# DC_AC_Inverter.net
KiCad netlist of a schematic drawn in Altium Designer
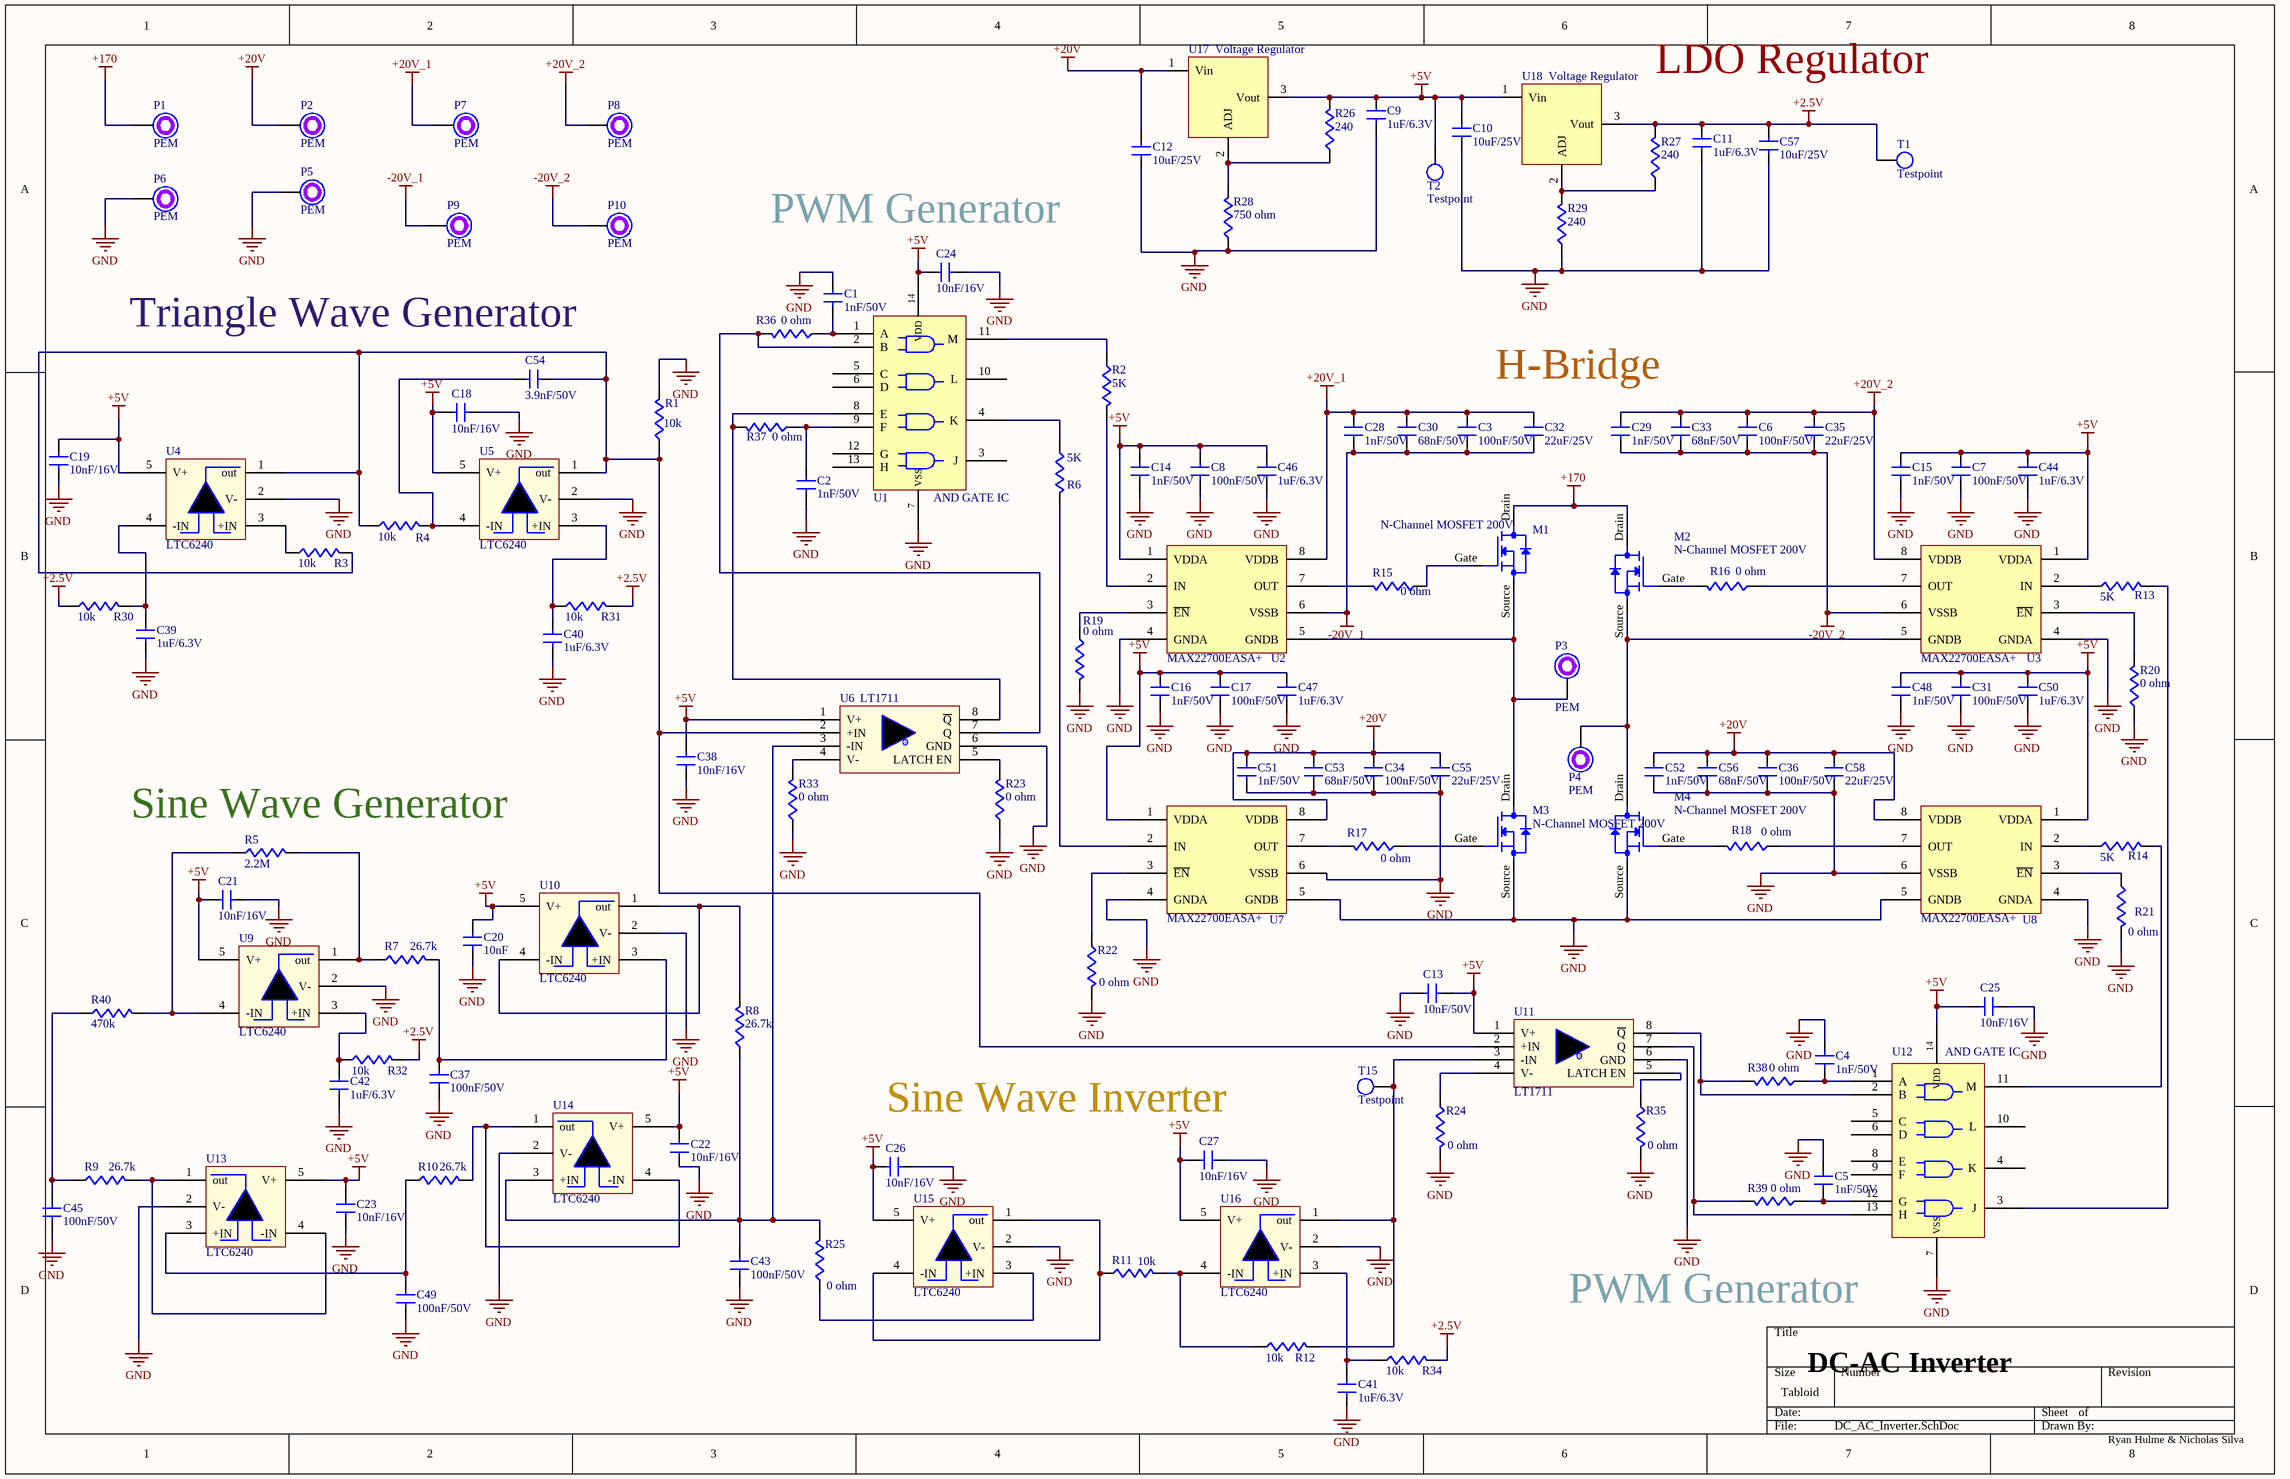
[diagram p0: DC_AC_Inverter.SchDoc]

(export (version "E")
  (design (tool "Eeschema 10.0.6"))
  (components
    (comp (ref "C1")
      (value "1nF/50V")
      (footprint "Capacitor")
      (description "Multilayer Ceramic Capacitors Mlcc - Smd/Smt 50V 1000Pf X7R 0603 10%")
      (fields
        (field (name "MANUFACTURER") "KEMET")
        (field (name "MANUFACTURER PART NUMBER") "C0603C102K5RACTU")
      )
      (libsource (lib "MAX227") (part "C0603C102K5RACTU"))
    )
    (comp (ref "C2")
      (value "1nF/50V")
      (footprint "Capacitor")
      (description "Multilayer Ceramic Capacitors Mlcc - Smd/Smt 50V 1000Pf X7R 0603 10%")
      (fields
        (field (name "MANUFACTURER") "KEMET")
        (field (name "MANUFACTURER PART NUMBER") "C0603C102K5RACTU")
      )
      (libsource (lib "MAX227") (part "C0603C102K5RACTU"))
    )
    (comp (ref "C3")
      (value "100nF/50V")
      (footprint "Capacitor")
      (description "50V 100nF X7R ±10% 0603 Multilayer Ceramic Capacitors MLCC - SMD/SMT ROHS")
      (fields
        (field (name "MANUFACTURER") "KEMET")
        (field (name "MANUFACTURER PART NUMBER") "C0603C104K5RACTU")
      )
      (libsource (lib "MAX227") (part "C0603C104K5RACTU"))
    )
    (comp (ref "C4")
      (value "1nF/50V")
      (footprint "Capacitor")
      (description "Multilayer Ceramic Capacitors Mlcc - Smd/Smt 50V 1000Pf X7R 0603 10%")
      (fields
        (field (name "MANUFACTURER") "KEMET")
        (field (name "MANUFACTURER PART NUMBER") "C0603C102K5RACTU")
      )
      (libsource (lib "MAX227") (part "C0603C102K5RACTU"))
    )
    (comp (ref "C5")
      (value "1nF/50V")
      (footprint "Capacitor")
      (description "Multilayer Ceramic Capacitors Mlcc - Smd/Smt 50V 1000Pf X7R 0603 10%")
      (fields
        (field (name "MANUFACTURER") "KEMET")
        (field (name "MANUFACTURER PART NUMBER") "C0603C102K5RACTU")
      )
      (libsource (lib "MAX227") (part "C0603C102K5RACTU"))
    )
    (comp (ref "C6")
      (value "100nF/50V")
      (footprint "Capacitor")
      (description "50V 100nF X7R ±10% 0603 Multilayer Ceramic Capacitors MLCC - SMD/SMT ROHS")
      (fields
        (field (name "MANUFACTURER") "KEMET")
        (field (name "MANUFACTURER PART NUMBER") "C0603C104K5RACTU")
      )
      (libsource (lib "MAX227") (part "C0603C104K5RACTU"))
    )
    (comp (ref "C7")
      (value "100nF/50V")
      (footprint "Capacitor")
      (description "50V 100nF X7R ±10% 0603 Multilayer Ceramic Capacitors MLCC - SMD/SMT ROHS")
      (fields
        (field (name "MANUFACTURER") "KEMET")
        (field (name "MANUFACTURER PART NUMBER") "C0603C104K5RACTU")
      )
      (libsource (lib "MAX227") (part "C0603C104K5RACTU"))
    )
    (comp (ref "C8")
      (value "100nF/50V")
      (footprint "Capacitor")
      (description "50V 100nF X7R ±10% 0603 Multilayer Ceramic Capacitors MLCC - SMD/SMT ROHS")
      (fields
        (field (name "MANUFACTURER") "KEMET")
        (field (name "MANUFACTURER PART NUMBER") "C0603C104K5RACTU")
      )
      (libsource (lib "MAX227") (part "C0603C104K5RACTU"))
    )
    (comp (ref "C9")
      (value "1uF/6.3V")
      (footprint "Capacitor")
      (description "High Value Multilayer Ceramic Capacitors (High dielectric type) ¦ CAP CER 1UF 6.3V X5R 0402")
      (fields
        (field (name "MANUFACTURER") "Taiyo Yuden")
        (field (name "MANUFACTURER PART NUMBER") "JMK105BJ105KV-F")
      )
      (libsource (lib "MAX227") (part "JMK105BJ105KV-F"))
    )
    (comp (ref "C10")
      (value "10uF/25V")
      (footprint "Capacitor")
      (description "25V 10uF X5R ±20% 0603 Multilayer Ceramic Capacitors MLCC - SMD/SMT ROHS")
      (fields
        (field (name "MANUFACTURER") "Samsung Electro-Mechanics")
        (field (name "MANUFACTURER PART NUMBER") "CL10A106MA8NRNC")
      )
      (libsource (lib "MAX227") (part "CL10A106MA8NRNC"))
    )
    (comp (ref "C11")
      (value "1uF/6.3V")
      (footprint "Capacitor")
      (description "High Value Multilayer Ceramic Capacitors (High dielectric type) ¦ CAP CER 1UF 6.3V X5R 0402")
      (fields
        (field (name "MANUFACTURER") "Taiyo Yuden")
        (field (name "MANUFACTURER PART NUMBER") "JMK105BJ105KV-F")
      )
      (libsource (lib "MAX227") (part "JMK105BJ105KV-F"))
    )
    (comp (ref "C12")
      (value "10uF/25V")
      (footprint "Capacitor")
      (description "25V 10uF X5R ±20% 0603 Multilayer Ceramic Capacitors MLCC - SMD/SMT ROHS")
      (fields
        (field (name "MANUFACTURER") "Samsung Electro-Mechanics")
        (field (name "MANUFACTURER PART NUMBER") "CL10A106MA8NRNC")
      )
      (libsource (lib "MAX227") (part "CL10A106MA8NRNC"))
    )
    (comp (ref "C13")
      (value "10nF/50V")
      (footprint "Capacitor")
      (description "16V 10nF X7R ±10% 0402 Multilayer Ceramic Capacitors MLCC - SMD/SMT ROHS")
      (fields
        (field (name "MANUFACTURER") "Murata")
        (field (name "MANUFACTURER PART NUMBER") "GRM155R71C103KA01D")
      )
      (libsource (lib "MAX227") (part "GRM155R71C103KA01D"))
    )
    (comp (ref "C14")
      (value "1nF/50V")
      (footprint "Capacitor")
      (description "Multilayer Ceramic Capacitors Mlcc - Smd/Smt 50V 1000Pf X7R 0603 10%")
      (fields
        (field (name "MANUFACTURER") "KEMET")
        (field (name "MANUFACTURER PART NUMBER") "C0603C102K5RACTU")
      )
      (libsource (lib "MAX227") (part "C0603C102K5RACTU"))
    )
    (comp (ref "C15")
      (value "1nF/50V")
      (footprint "Capacitor")
      (description "Multilayer Ceramic Capacitors Mlcc - Smd/Smt 50V 1000Pf X7R 0603 10%")
      (fields
        (field (name "MANUFACTURER") "KEMET")
        (field (name "MANUFACTURER PART NUMBER") "C0603C102K5RACTU")
      )
      (libsource (lib "MAX227") (part "C0603C102K5RACTU"))
    )
    (comp (ref "C16")
      (value "1nF/50V")
      (footprint "Capacitor")
      (description "Multilayer Ceramic Capacitors Mlcc - Smd/Smt 50V 1000Pf X7R 0603 10%")
      (fields
        (field (name "MANUFACTURER") "KEMET")
        (field (name "MANUFACTURER PART NUMBER") "C0603C102K5RACTU")
      )
      (libsource (lib "MAX227") (part "C0603C102K5RACTU"))
    )
    (comp (ref "C17")
      (value "100nF/50V")
      (footprint "Capacitor")
      (description "50V 100nF X7R ±10% 0603 Multilayer Ceramic Capacitors MLCC - SMD/SMT ROHS")
      (fields
        (field (name "MANUFACTURER") "KEMET")
        (field (name "MANUFACTURER PART NUMBER") "C0603C104K5RACTU")
      )
      (libsource (lib "MAX227") (part "C0603C104K5RACTU"))
    )
    (comp (ref "C18")
      (value "10nF/16V")
      (footprint "Capacitor")
      (description "16V 10nF X7R ±10% 0402 Multilayer Ceramic Capacitors MLCC - SMD/SMT ROHS")
      (fields
        (field (name "MANUFACTURER") "Murata")
        (field (name "MANUFACTURER PART NUMBER") "GRM155R71C103KA01D")
      )
      (libsource (lib "MAX227") (part "GRM155R71C103KA01D"))
    )
    (comp (ref "C19")
      (value "10nF/16V")
      (footprint "Capacitor")
      (description "16V 10nF X7R ±10% 0402 Multilayer Ceramic Capacitors MLCC - SMD/SMT ROHS")
      (fields
        (field (name "MANUFACTURER") "Murata")
        (field (name "MANUFACTURER PART NUMBER") "GRM155R71C103KA01D")
      )
      (libsource (lib "MAX227") (part "GRM155R71C103KA01D"))
    )
    (comp (ref "C20")
      (value "10nF")
      (footprint "Capacitor")
      (description "16V 10nF X7R ±10% 0402 Multilayer Ceramic Capacitors MLCC - SMD/SMT ROHS")
      (fields
        (field (name "MANUFACTURER") "Murata")
        (field (name "MANUFACTURER PART NUMBER") "GRM155R71C103KA01D")
      )
      (libsource (lib "MAX227") (part "GRM155R71C103KA01D"))
    )
    (comp (ref "C21")
      (value "10nF/16V")
      (footprint "Capacitor")
      (description "16V 10nF X7R ±10% 0402 Multilayer Ceramic Capacitors MLCC - SMD/SMT ROHS")
      (fields
        (field (name "MANUFACTURER") "Murata")
        (field (name "MANUFACTURER PART NUMBER") "GRM155R71C103KA01D")
      )
      (libsource (lib "MAX227") (part "GRM155R71C103KA01D"))
    )
    (comp (ref "C22")
      (value "10nF/16V")
      (footprint "Capacitor")
      (description "16V 10nF X7R ±10% 0402 Multilayer Ceramic Capacitors MLCC - SMD/SMT ROHS")
      (fields
        (field (name "MANUFACTURER") "Murata")
        (field (name "MANUFACTURER PART NUMBER") "GRM155R71C103KA01D")
      )
      (libsource (lib "MAX227") (part "GRM155R71C103KA01D"))
    )
    (comp (ref "C23")
      (value "10nF/16V")
      (footprint "Capacitor")
      (description "16V 10nF X7R ±10% 0402 Multilayer Ceramic Capacitors MLCC - SMD/SMT ROHS")
      (fields
        (field (name "MANUFACTURER") "Murata")
        (field (name "MANUFACTURER PART NUMBER") "GRM155R71C103KA01D")
      )
      (libsource (lib "MAX227") (part "GRM155R71C103KA01D"))
    )
    (comp (ref "C24")
      (value "10nF/16V")
      (footprint "Capacitor")
      (description "16V 10nF X7R ±10% 0402 Multilayer Ceramic Capacitors MLCC - SMD/SMT ROHS")
      (fields
        (field (name "MANUFACTURER") "Murata")
        (field (name "MANUFACTURER PART NUMBER") "GRM155R71C103KA01D")
      )
      (libsource (lib "MAX227") (part "GRM155R71C103KA01D"))
    )
    (comp (ref "C25")
      (value "10nF/16V")
      (footprint "Capacitor")
      (description "16V 10nF X7R ±10% 0402 Multilayer Ceramic Capacitors MLCC - SMD/SMT ROHS")
      (fields
        (field (name "MANUFACTURER") "Murata")
        (field (name "MANUFACTURER PART NUMBER") "GRM155R71C103KA01D")
      )
      (libsource (lib "MAX227") (part "GRM155R71C103KA01D"))
    )
    (comp (ref "C26")
      (value "10nF/16V")
      (footprint "Capacitor")
      (description "16V 10nF X7R ±10% 0402 Multilayer Ceramic Capacitors MLCC - SMD/SMT ROHS")
      (fields
        (field (name "MANUFACTURER") "Murata")
        (field (name "MANUFACTURER PART NUMBER") "GRM155R71C103KA01D")
      )
      (libsource (lib "MAX227") (part "GRM155R71C103KA01D"))
    )
    (comp (ref "C27")
      (value "10nF/16V")
      (footprint "Capacitor")
      (description "16V 10nF X7R ±10% 0402 Multilayer Ceramic Capacitors MLCC - SMD/SMT ROHS")
      (fields
        (field (name "MANUFACTURER") "Murata")
        (field (name "MANUFACTURER PART NUMBER") "GRM155R71C103KA01D")
      )
      (libsource (lib "MAX227") (part "GRM155R71C103KA01D"))
    )
    (comp (ref "C28")
      (value "1nF/50V")
      (footprint "Capacitor")
      (description "Multilayer Ceramic Capacitors Mlcc - Smd/Smt 50V 1000Pf X7R 0603 10%")
      (fields
        (field (name "MANUFACTURER") "KEMET")
        (field (name "MANUFACTURER PART NUMBER") "C0603C102K5RACTU")
      )
      (libsource (lib "MAX227") (part "C0603C102K5RACTU"))
    )
    (comp (ref "C29")
      (value "1nF/50V")
      (footprint "Capacitor")
      (description "Multilayer Ceramic Capacitors Mlcc - Smd/Smt 50V 1000Pf X7R 0603 10%")
      (fields
        (field (name "MANUFACTURER") "KEMET")
        (field (name "MANUFACTURER PART NUMBER") "C0603C102K5RACTU")
      )
      (libsource (lib "MAX227") (part "C0603C102K5RACTU"))
    )
    (comp (ref "C30")
      (value "68nF/50V")
      (footprint "Capacitor")
      (fields
        (field (name "MANUFACTURER") "KEMET")
        (field (name "MANUFACTURER PART NUMBER") "C0603C683K5RACTU")
        (field (name "TOLERANCE") "10%")
      )
      (libsource (lib "MAX227") (part "C0603C683K5RACTU"))
    )
    (comp (ref "C31")
      (value "100nF/50V")
      (footprint "Capacitor")
      (description "50V 100nF X7R ±10% 0603 Multilayer Ceramic Capacitors MLCC - SMD/SMT ROHS")
      (fields
        (field (name "MANUFACTURER") "KEMET")
        (field (name "MANUFACTURER PART NUMBER") "C0603C104K5RACTU")
      )
      (libsource (lib "MAX227") (part "C0603C104K5RACTU"))
    )
    (comp (ref "C32")
      (value "22uF/25V")
      (footprint "Capacitor")
      (fields
        (field (name "MANUFACTURER") "Murata")
        (field (name "MANUFACTURER PART NUMBER") "GRM188C61E226ME01J")
        (field (name "TOLERANCE") "20%")
      )
      (libsource (lib "MAX227") (part "GRM188C61E226ME01J"))
    )
    (comp (ref "C33")
      (value "68nF/50V")
      (footprint "Capacitor")
      (fields
        (field (name "MANUFACTURER") "KEMET")
        (field (name "MANUFACTURER PART NUMBER") "C0603C683K5RACTU")
        (field (name "TOLERANCE") "10%")
      )
      (libsource (lib "MAX227") (part "C0603C683K5RACTU"))
    )
    (comp (ref "C34")
      (value "100nF/50V")
      (footprint "Capacitor")
      (description "50V 100nF X7R ±10% 0603 Multilayer Ceramic Capacitors MLCC - SMD/SMT ROHS")
      (fields
        (field (name "MANUFACTURER") "KEMET")
        (field (name "MANUFACTURER PART NUMBER") "C0603C104K5RACTU")
      )
      (libsource (lib "MAX227") (part "C0603C104K5RACTU"))
    )
    (comp (ref "C35")
      (value "22uF/25V")
      (footprint "Capacitor")
      (fields
        (field (name "MANUFACTURER") "Murata")
        (field (name "MANUFACTURER PART NUMBER") "GRM188C61E226ME01J")
        (field (name "TOLERANCE") "20%")
      )
      (libsource (lib "MAX227") (part "GRM188C61E226ME01J"))
    )
    (comp (ref "C36")
      (value "100nF/50V")
      (footprint "Capacitor")
      (description "50V 100nF X7R ±10% 0603 Multilayer Ceramic Capacitors MLCC - SMD/SMT ROHS")
      (fields
        (field (name "MANUFACTURER") "KEMET")
        (field (name "MANUFACTURER PART NUMBER") "C0603C104K5RACTU")
      )
      (libsource (lib "MAX227") (part "C0603C104K5RACTU"))
    )
    (comp (ref "C37")
      (value "100nF/50V")
      (footprint "Capacitor")
      (description "50V 100nF X7R ±10% 0603 Multilayer Ceramic Capacitors MLCC - SMD/SMT ROHS")
      (fields
        (field (name "MANUFACTURER") "KEMET")
        (field (name "MANUFACTURER PART NUMBER") "C0603C104K5RACTU")
      )
      (libsource (lib "MAX227") (part "C0603C104K5RACTU"))
    )
    (comp (ref "C38")
      (value "10nF/16V")
      (footprint "Capacitor")
      (description "16V 10nF X7R ±10% 0402 Multilayer Ceramic Capacitors MLCC - SMD/SMT ROHS")
      (fields
        (field (name "MANUFACTURER") "Murata")
        (field (name "MANUFACTURER PART NUMBER") "GRM155R71C103KA01D")
      )
      (libsource (lib "MAX227") (part "GRM155R71C103KA01D"))
    )
    (comp (ref "C39")
      (value "1uF/6.3V")
      (footprint "Capacitor")
      (description "High Value Multilayer Ceramic Capacitors (High dielectric type) ¦ CAP CER 1UF 6.3V X5R 0402")
      (fields
        (field (name "MANUFACTURER") "Taiyo Yuden")
        (field (name "MANUFACTURER PART NUMBER") "JMK105BJ105KV-F")
      )
      (libsource (lib "MAX227") (part "JMK105BJ105KV-F"))
    )
    (comp (ref "C40")
      (value "1uF/6.3V")
      (footprint "Capacitor")
      (description "High Value Multilayer Ceramic Capacitors (High dielectric type) ¦ CAP CER 1UF 6.3V X5R 0402")
      (fields
        (field (name "MANUFACTURER") "Taiyo Yuden")
        (field (name "MANUFACTURER PART NUMBER") "JMK105BJ105KV-F")
      )
      (libsource (lib "MAX227") (part "JMK105BJ105KV-F"))
    )
    (comp (ref "C41")
      (value "1uF/6.3V")
      (footprint "Capacitor")
      (description "High Value Multilayer Ceramic Capacitors (High dielectric type) ¦ CAP CER 1UF 6.3V X5R 0402")
      (fields
        (field (name "MANUFACTURER") "Taiyo Yuden")
        (field (name "MANUFACTURER PART NUMBER") "JMK105BJ105KV-F")
      )
      (libsource (lib "MAX227") (part "JMK105BJ105KV-F"))
    )
    (comp (ref "C42")
      (value "1uF/6.3V")
      (footprint "Capacitor")
      (description "High Value Multilayer Ceramic Capacitors (High dielectric type) ¦ CAP CER 1UF 6.3V X5R 0402")
      (fields
        (field (name "MANUFACTURER") "Taiyo Yuden")
        (field (name "MANUFACTURER PART NUMBER") "JMK105BJ105KV-F")
      )
      (libsource (lib "MAX227") (part "JMK105BJ105KV-F"))
    )
    (comp (ref "C43")
      (value "100nF/50V")
      (footprint "Capacitor")
      (description "50V 100nF X7R ±10% 0603 Multilayer Ceramic Capacitors MLCC - SMD/SMT ROHS")
      (fields
        (field (name "MANUFACTURER") "KEMET")
        (field (name "MANUFACTURER PART NUMBER") "C0603C104K5RACTU")
      )
      (libsource (lib "MAX227") (part "C0603C104K5RACTU"))
    )
    (comp (ref "C44")
      (value "1uF/6.3V")
      (footprint "Capacitor")
      (description "High Value Multilayer Ceramic Capacitors (High dielectric type) ¦ CAP CER 1UF 6.3V X5R 0402")
      (fields
        (field (name "MANUFACTURER") "Taiyo Yuden")
        (field (name "MANUFACTURER PART NUMBER") "JMK105BJ105KV-F")
      )
      (libsource (lib "MAX227") (part "JMK105BJ105KV-F"))
    )
    (comp (ref "C45")
      (value "100nF/50V")
      (footprint "Capacitor")
      (description "50V 100nF X7R ±10% 0603 Multilayer Ceramic Capacitors MLCC - SMD/SMT ROHS")
      (fields
        (field (name "MANUFACTURER") "KEMET")
        (field (name "MANUFACTURER PART NUMBER") "C0603C104K5RACTU")
      )
      (libsource (lib "MAX227") (part "C0603C104K5RACTU"))
    )
    (comp (ref "C46")
      (value "1uF/6.3V")
      (footprint "Capacitor")
      (description "High Value Multilayer Ceramic Capacitors (High dielectric type) ¦ CAP CER 1UF 6.3V X5R 0402")
      (fields
        (field (name "MANUFACTURER") "Taiyo Yuden")
        (field (name "MANUFACTURER PART NUMBER") "JMK105BJ105KV-F")
      )
      (libsource (lib "MAX227") (part "JMK105BJ105KV-F"))
    )
    (comp (ref "C47")
      (value "1uF/6.3V")
      (footprint "Capacitor")
      (description "High Value Multilayer Ceramic Capacitors (High dielectric type) ¦ CAP CER 1UF 6.3V X5R 0402")
      (fields
        (field (name "MANUFACTURER") "Taiyo Yuden")
        (field (name "MANUFACTURER PART NUMBER") "JMK105BJ105KV-F")
      )
      (libsource (lib "MAX227") (part "JMK105BJ105KV-F"))
    )
    (comp (ref "C48")
      (value "1nF/50V")
      (footprint "Capacitor")
      (description "Multilayer Ceramic Capacitors Mlcc - Smd/Smt 50V 1000Pf X7R 0603 10%")
      (fields
        (field (name "MANUFACTURER") "KEMET")
        (field (name "MANUFACTURER PART NUMBER") "C0603C102K5RACTU")
      )
      (libsource (lib "MAX227") (part "C0603C102K5RACTU"))
    )
    (comp (ref "C49")
      (value "100nF/50V")
      (footprint "Capacitor")
      (description "50V 100nF X7R ±10% 0603 Multilayer Ceramic Capacitors MLCC - SMD/SMT ROHS")
      (fields
        (field (name "MANUFACTURER") "KEMET")
        (field (name "MANUFACTURER PART NUMBER") "C0603C104K5RACTU")
      )
      (libsource (lib "MAX227") (part "C0603C104K5RACTU"))
    )
    (comp (ref "C50")
      (value "1uF/6.3V")
      (footprint "Capacitor")
      (description "High Value Multilayer Ceramic Capacitors (High dielectric type) ¦ CAP CER 1UF 6.3V X5R 0402")
      (fields
        (field (name "MANUFACTURER") "Taiyo Yuden")
        (field (name "MANUFACTURER PART NUMBER") "JMK105BJ105KV-F")
      )
      (libsource (lib "MAX227") (part "JMK105BJ105KV-F"))
    )
    (comp (ref "C51")
      (value "1nF/50V")
      (footprint "Capacitor")
      (description "Multilayer Ceramic Capacitors Mlcc - Smd/Smt 50V 1000Pf X7R 0603 10%")
      (fields
        (field (name "MANUFACTURER") "KEMET")
        (field (name "MANUFACTURER PART NUMBER") "C0603C102K5RACTU")
      )
      (libsource (lib "MAX227") (part "C0603C102K5RACTU"))
    )
    (comp (ref "C52")
      (value "1nF/50V")
      (footprint "Capacitor")
      (description "Multilayer Ceramic Capacitors Mlcc - Smd/Smt 50V 1000Pf X7R 0603 10%")
      (fields
        (field (name "MANUFACTURER") "KEMET")
        (field (name "MANUFACTURER PART NUMBER") "C0603C102K5RACTU")
      )
      (libsource (lib "MAX227") (part "C0603C102K5RACTU"))
    )
    (comp (ref "C53")
      (value "68nF/50V")
      (footprint "Capacitor")
      (fields
        (field (name "MANUFACTURER") "KEMET")
        (field (name "MANUFACTURER PART NUMBER") "C0603C683K5RACTU")
        (field (name "TOLERANCE") "10%")
      )
      (libsource (lib "MAX227") (part "C0603C683K5RACTU"))
    )
    (comp (ref "C54")
      (value "3.9nF/50V")
      (footprint "Capacitor")
      (description "0603 3.9 nF 50 V ±5 % Tolerance C0G SMT Multilayer Ceramic Capacitor")
      (fields
        (field (name "MANUFACTURER") "Murata")
        (field (name "MANUFACTURER PART NUMBER") "GCM1885C1H392JA16D")
      )
      (libsource (lib "MAX227") (part "GCM1885C1H392JA16D"))
    )
    (comp (ref "C55")
      (value "22uF/25V")
      (footprint "Capacitor")
      (fields
        (field (name "MANUFACTURER") "Murata")
        (field (name "MANUFACTURER PART NUMBER") "GRM188C61E226ME01J")
        (field (name "TOLERANCE") "20%")
      )
      (libsource (lib "MAX227") (part "GRM188C61E226ME01J"))
    )
    (comp (ref "C56")
      (value "68nF/50V")
      (footprint "Capacitor")
      (fields
        (field (name "MANUFACTURER") "KEMET")
        (field (name "MANUFACTURER PART NUMBER") "C0603C683K5RACTU")
        (field (name "TOLERANCE") "10%")
      )
      (libsource (lib "MAX227") (part "C0603C683K5RACTU"))
    )
    (comp (ref "C57")
      (value "10uF/25V")
      (footprint "Capacitor")
      (description "25V 10uF X5R ±20% 0603 Multilayer Ceramic Capacitors MLCC - SMD/SMT ROHS")
      (fields
        (field (name "MANUFACTURER") "Samsung Electro-Mechanics")
        (field (name "MANUFACTURER PART NUMBER") "CL10A106MA8NRNC")
      )
      (libsource (lib "MAX227") (part "CL10A106MA8NRNC"))
    )
    (comp (ref "C58")
      (value "22uF/25V")
      (footprint "Capacitor")
      (fields
        (field (name "MANUFACTURER") "Murata")
        (field (name "MANUFACTURER PART NUMBER") "GRM188C61E226ME01J")
        (field (name "TOLERANCE") "20%")
      )
      (libsource (lib "MAX227") (part "GRM188C61E226ME01J"))
    )
    (comp (ref "M1")
      (value "N-Channel MOSFET 200V")
      (footprint "SOT89-254P1058X483-3N")
      (description "Trans MOSFET N-CH 200V 15.4A 3-Pin(2+Tab) D2PAK T/R")
      (fields
        (field (name "MANUFACTURER") "Infineon")
        (field (name "MANUFACTURER PART NUMBER") "IPB068N20NM6ATMA1")
      )
      (libsource (lib "MAX227") (part "IPB068N20NM6ATMA1"))
    )
    (comp (ref "M2")
      (value "N-Channel MOSFET 200V")
      (footprint "SOT89-254P1058X483-3N")
      (description "Trans MOSFET N-CH 200V 15.4A 3-Pin(2+Tab) D2PAK T/R")
      (fields
        (field (name "MANUFACTURER") "Infineon")
        (field (name "MANUFACTURER PART NUMBER") "IPB068N20NM6ATMA1")
      )
      (libsource (lib "MAX227") (part "IPB068N20NM6ATMA1"))
    )
    (comp (ref "M3")
      (value "N-Channel MOSFET 200V")
      (footprint "SOT89-254P1058X483-3N")
      (description "Trans MOSFET N-CH 200V 15.4A 3-Pin(2+Tab) D2PAK T/R")
      (fields
        (field (name "MANUFACTURER") "Infineon")
        (field (name "MANUFACTURER PART NUMBER") "IPB068N20NM6ATMA1")
      )
      (libsource (lib "MAX227") (part "IPB068N20NM6ATMA1"))
    )
    (comp (ref "M4")
      (value "N-Channel MOSFET 200V")
      (footprint "SOT89-254P1058X483-3N")
      (description "Trans MOSFET N-CH 200V 15.4A 3-Pin(2+Tab) D2PAK T/R")
      (fields
        (field (name "MANUFACTURER") "Infineon")
        (field (name "MANUFACTURER PART NUMBER") "IPB068N20NM6ATMA1")
      )
      (libsource (lib "MAX227") (part "IPB068N20NM6ATMA1"))
    )
    (comp (ref "P1")
      (value "PEM")
      (footprint "PEMs")
      (description "PEM:\r\nSMTSOB-632-4ET")
      (libsource (lib "MAX227") (part "PEMs"))
    )
    (comp (ref "P2")
      (value "PEM")
      (footprint "PEMs")
      (description "PEM:\r\nSMTSOB-632-4ET")
      (libsource (lib "MAX227") (part "PEMs"))
    )
    (comp (ref "P3")
      (value "PEM")
      (footprint "PEMs")
      (description "PEM:\r\nSMTSOB-632-4ET")
      (libsource (lib "MAX227") (part "PEMs"))
    )
    (comp (ref "P4")
      (value "PEM")
      (footprint "PEMs")
      (description "PEM:\r\nSMTSOB-632-4ET")
      (libsource (lib "MAX227") (part "PEMs"))
    )
    (comp (ref "P5")
      (value "PEM")
      (footprint "PEMs")
      (description "PEM:\r\nSMTSOB-632-4ET")
      (libsource (lib "MAX227") (part "PEMs"))
    )
    (comp (ref "P6")
      (value "PEM")
      (footprint "PEMs")
      (description "PEM:\r\nSMTSOB-632-4ET")
      (libsource (lib "MAX227") (part "PEMs"))
    )
    (comp (ref "P7")
      (value "PEM")
      (footprint "PEMs")
      (description "PEM:\r\nSMTSOB-632-4ET")
      (libsource (lib "MAX227") (part "PEMs"))
    )
    (comp (ref "P8")
      (value "PEM")
      (footprint "PEMs")
      (description "PEM:\r\nSMTSOB-632-4ET")
      (libsource (lib "MAX227") (part "PEMs"))
    )
    (comp (ref "P9")
      (value "PEM")
      (footprint "PEMs")
      (description "PEM:\r\nSMTSOB-632-4ET")
      (libsource (lib "MAX227") (part "PEMs"))
    )
    (comp (ref "P10")
      (value "PEM")
      (footprint "PEMs")
      (description "PEM:\r\nSMTSOB-632-4ET")
      (libsource (lib "MAX227") (part "PEMs"))
    )
    (comp (ref "R1")
      (value "10k")
      (footprint "R0805")
      (description "Res Metal Foil 2917 10K Ohm 0.01% 3/5W 2ppm/C Molded SMD T/R - Custom Tape W/Lea")
      (fields
        (field (name "MANUFACTURER") "VPG Foil Resistors")
        (field (name "MANUFACTURER PART NUMBER") "Y116910K0000T9R")
      )
      (libsource (lib "MAX227") (part "Y116910K0000T9R"))
    )
    (comp (ref "R2")
      (value "5K")
      (footprint "Resis5k")
      (description "Res Thin Film 0805 5K Ohm 0.1% 0.2W(1/5W) ±25ppm/C Sulfur Resistant Pad SMD Medical T/R")
      (fields
        (field (name "MANUFACTURER") "Vishay")
        (field (name "MANUFACTURER PART NUMBER") "PNM0805E5001BST5")
      )
      (libsource (lib "MAX227") (part "PNM0805E5001BST5"))
    )
    (comp (ref "R3")
      (value "10k")
      (footprint "R0805")
      (description "Res Metal Foil 2917 10K Ohm 0.01% 3/5W 2ppm/C Molded SMD T/R - Custom Tape W/Lea")
      (fields
        (field (name "MANUFACTURER") "VPG Foil Resistors")
        (field (name "MANUFACTURER PART NUMBER") "Y116910K0000T9R")
      )
      (libsource (lib "MAX227") (part "Y116910K0000T9R"))
    )
    (comp (ref "R4")
      (value "10k")
      (footprint "R0805")
      (description "Res Metal Foil 2917 10K Ohm 0.01% 3/5W 2ppm/C Molded SMD T/R - Custom Tape W/Lea")
      (fields
        (field (name "MANUFACTURER") "VPG Foil Resistors")
        (field (name "MANUFACTURER PART NUMBER") "Y116910K0000T9R")
      )
      (libsource (lib "MAX227") (part "Y116910K0000T9R"))
    )
    (comp (ref "R5")
      (value "2.2M")
      (footprint "Resistor-26.7")
      (description "62.5mW Thick Film Resistors 50V ±100ppm/℃ ±1% 2.2MΩ 0402 Chip Resistor - Surface Mount ROHS")
      (fields
        (field (name "MANUFACTURER") "Yageo Group")
        (field (name "MANUFACTURER PART NUMBER") "RC0402FR-072M2L")
      )
      (libsource (lib "MAX227") (part "RC0402FR-072M2L"))
    )
    (comp (ref "R6")
      (value "5K")
      (footprint "Resis5k")
      (description "Res Thin Film 0805 5K Ohm 0.1% 0.2W(1/5W) ±25ppm/C Sulfur Resistant Pad SMD Medical T/R")
      (fields
        (field (name "MANUFACTURER") "Vishay")
        (field (name "MANUFACTURER PART NUMBER") "PNM0805E5001BST5")
      )
      (libsource (lib "MAX227") (part "PNM0805E5001BST5"))
    )
    (comp (ref "R7")
      (value "26.7k")
      (footprint "Resistor-26.7")
      (description "Res Thick Film 0402 26.7K Ohm 1% 1/16W ±100ppm/°C Molded SMD Paper T/R")
      (fields
        (field (name "MANUFACTURER") "Yageo Group")
        (field (name "MANUFACTURER PART NUMBER") "RC0402FR-0726K7L")
      )
      (libsource (lib "MAX227") (part "RC0402FR-0726K7L"))
    )
    (comp (ref "R8")
      (value "26.7k")
      (footprint "Resistor-26.7")
      (description "Res Thick Film 0402 26.7K Ohm 1% 1/16W ±100ppm/°C Molded SMD Paper T/R")
      (fields
        (field (name "MANUFACTURER") "Yageo Group")
        (field (name "MANUFACTURER PART NUMBER") "RC0402FR-0726K7L")
      )
      (libsource (lib "MAX227") (part "RC0402FR-0726K7L"))
    )
    (comp (ref "R9")
      (value "26.7k")
      (footprint "Resistor-26.7")
      (description "Res Thick Film 0402 26.7K Ohm 1% 1/16W ±100ppm/°C Molded SMD Paper T/R")
      (fields
        (field (name "MANUFACTURER") "Yageo Group")
        (field (name "MANUFACTURER PART NUMBER") "RC0402FR-0726K7L")
      )
      (libsource (lib "MAX227") (part "RC0402FR-0726K7L"))
    )
    (comp (ref "R10")
      (value "26.7k")
      (footprint "Resistor-26.7")
      (description "Res Thick Film 0402 26.7K Ohm 1% 1/16W ±100ppm/°C Molded SMD Paper T/R")
      (fields
        (field (name "MANUFACTURER") "Yageo Group")
        (field (name "MANUFACTURER PART NUMBER") "RC0402FR-0726K7L")
      )
      (libsource (lib "MAX227") (part "RC0402FR-0726K7L"))
    )
    (comp (ref "R11")
      (value "10k")
      (footprint "R0805")
      (description "Res Metal Foil 2917 10K Ohm 0.01% 3/5W 2ppm/C Molded SMD T/R - Custom Tape W/Lea")
      (fields
        (field (name "MANUFACTURER") "VPG Foil Resistors")
        (field (name "MANUFACTURER PART NUMBER") "Y116910K0000T9R")
      )
      (libsource (lib "MAX227") (part "Y116910K0000T9R"))
    )
    (comp (ref "R12")
      (value "10k")
      (footprint "R0805")
      (description "Res Metal Foil 2917 10K Ohm 0.01% 3/5W 2ppm/C Molded SMD T/R - Custom Tape W/Lea")
      (fields
        (field (name "MANUFACTURER") "VPG Foil Resistors")
        (field (name "MANUFACTURER PART NUMBER") "Y116910K0000T9R")
      )
      (libsource (lib "MAX227") (part "Y116910K0000T9R"))
    )
    (comp (ref "R13")
      (value "5K")
      (footprint "Resis5k")
      (description "Res Thin Film 0805 5K Ohm 0.1% 0.2W(1/5W) ±25ppm/C Sulfur Resistant Pad SMD Medical T/R")
      (fields
        (field (name "MANUFACTURER") "Vishay")
        (field (name "MANUFACTURER PART NUMBER") "PNM0805E5001BST5")
      )
      (libsource (lib "MAX227") (part "PNM0805E5001BST5"))
    )
    (comp (ref "R14")
      (value "5K")
      (footprint "Resis5k")
      (description "Res Thin Film 0805 5K Ohm 0.1% 0.2W(1/5W) ±25ppm/C Sulfur Resistant Pad SMD Medical T/R")
      (fields
        (field (name "MANUFACTURER") "Vishay")
        (field (name "MANUFACTURER PART NUMBER") "PNM0805E5001BST5")
      )
      (libsource (lib "MAX227") (part "PNM0805E5001BST5"))
    )
    (comp (ref "R15")
      (value "0 ohm")
      (footprint "Resistor-26.7")
      (description "GENERAL PURPOSE CHIP RESISTOR Metal Glaze/thick Film, 0.0625W, 0ohm, Surface Mount, 0402")
      (fields
        (field (name "MANUFACTURER") "Yageo Group")
        (field (name "MANUFACTURER PART NUMBER") "RC0402JR-070RL")
      )
      (libsource (lib "MAX227") (part "RC0402JR-070RL"))
    )
    (comp (ref "R16")
      (value "0 ohm")
      (footprint "Resistor-26.7")
      (description "GENERAL PURPOSE CHIP RESISTOR Metal Glaze/thick Film, 0.0625W, 0ohm, Surface Mount, 0402")
      (fields
        (field (name "MANUFACTURER") "Yageo Group")
        (field (name "MANUFACTURER PART NUMBER") "RC0402JR-070RL")
      )
      (libsource (lib "MAX227") (part "RC0402JR-070RL"))
    )
    (comp (ref "R17")
      (value "0 ohm")
      (footprint "Resistor-26.7")
      (description "GENERAL PURPOSE CHIP RESISTOR Metal Glaze/thick Film, 0.0625W, 0ohm, Surface Mount, 0402")
      (fields
        (field (name "MANUFACTURER") "Yageo Group")
        (field (name "MANUFACTURER PART NUMBER") "RC0402JR-070RL")
      )
      (libsource (lib "MAX227") (part "RC0402JR-070RL"))
    )
    (comp (ref "R18")
      (value "0 ohm")
      (footprint "Resistor-26.7")
      (description "GENERAL PURPOSE CHIP RESISTOR Metal Glaze/thick Film, 0.0625W, 0ohm, Surface Mount, 0402")
      (fields
        (field (name "MANUFACTURER") "Yageo Group")
        (field (name "MANUFACTURER PART NUMBER") "RC0402JR-070RL")
      )
      (libsource (lib "MAX227") (part "RC0402JR-070RL"))
    )
    (comp (ref "R19")
      (value "0 ohm")
      (footprint "Resistor-26.7")
      (description "GENERAL PURPOSE CHIP RESISTOR Metal Glaze/thick Film, 0.0625W, 0ohm, Surface Mount, 0402")
      (fields
        (field (name "MANUFACTURER") "Yageo Group")
        (field (name "MANUFACTURER PART NUMBER") "RC0402JR-070RL")
      )
      (libsource (lib "MAX227") (part "RC0402JR-070RL"))
    )
    (comp (ref "R20")
      (value "0 ohm")
      (footprint "Resistor-26.7")
      (description "GENERAL PURPOSE CHIP RESISTOR Metal Glaze/thick Film, 0.0625W, 0ohm, Surface Mount, 0402")
      (fields
        (field (name "MANUFACTURER") "Yageo Group")
        (field (name "MANUFACTURER PART NUMBER") "RC0402JR-070RL")
      )
      (libsource (lib "MAX227") (part "RC0402JR-070RL"))
    )
    (comp (ref "R21")
      (value "0 ohm")
      (footprint "Resistor-26.7")
      (description "GENERAL PURPOSE CHIP RESISTOR Metal Glaze/thick Film, 0.0625W, 0ohm, Surface Mount, 0402")
      (fields
        (field (name "MANUFACTURER") "Yageo Group")
        (field (name "MANUFACTURER PART NUMBER") "RC0402JR-070RL")
      )
      (libsource (lib "MAX227") (part "RC0402JR-070RL"))
    )
    (comp (ref "R22")
      (value "0 ohm")
      (footprint "Resistor-26.7")
      (description "GENERAL PURPOSE CHIP RESISTOR Metal Glaze/thick Film, 0.0625W, 0ohm, Surface Mount, 0402")
      (fields
        (field (name "MANUFACTURER") "Yageo Group")
        (field (name "MANUFACTURER PART NUMBER") "RC0402JR-070RL")
      )
      (libsource (lib "MAX227") (part "RC0402JR-070RL"))
    )
    (comp (ref "R23")
      (value "0 ohm")
      (footprint "Resistor-26.7")
      (description "GENERAL PURPOSE CHIP RESISTOR Metal Glaze/thick Film, 0.0625W, 0ohm, Surface Mount, 0402")
      (fields
        (field (name "MANUFACTURER") "Yageo Group")
        (field (name "MANUFACTURER PART NUMBER") "RC0402JR-070RL")
      )
      (libsource (lib "MAX227") (part "RC0402JR-070RL"))
    )
    (comp (ref "R24")
      (value "0 ohm")
      (footprint "Resistor-26.7")
      (description "GENERAL PURPOSE CHIP RESISTOR Metal Glaze/thick Film, 0.0625W, 0ohm, Surface Mount, 0402")
      (fields
        (field (name "MANUFACTURER") "Yageo Group")
        (field (name "MANUFACTURER PART NUMBER") "RC0402JR-070RL")
      )
      (libsource (lib "MAX227") (part "RC0402JR-070RL"))
    )
    (comp (ref "R25")
      (value "0 ohm")
      (footprint "Resistor-26.7")
      (description "GENERAL PURPOSE CHIP RESISTOR Metal Glaze/thick Film, 0.0625W, 0ohm, Surface Mount, 0402")
      (fields
        (field (name "MANUFACTURER") "Yageo Group")
        (field (name "MANUFACTURER PART NUMBER") "RC0402JR-070RL")
      )
      (libsource (lib "MAX227") (part "RC0402JR-070RL"))
    )
    (comp (ref "R26")
      (value "240")
      (footprint "Resistor-26.7")
      (description "Res Thick Film 0402 240 Ohm 1% 0.1W ±100ppm/°C Molded SMD Punched Carrier T/R")
      (fields
        (field (name "MANUFACTURER") "Panasonic")
        (field (name "MANUFACTURER PART NUMBER") "ERJ-2RKF2400X")
      )
      (libsource (lib "MAX227") (part "ERJ-2RKF2400X"))
    )
    (comp (ref "R27")
      (value "240")
      (footprint "Resistor-26.7")
      (description "Res Thick Film 0402 240 Ohm 1% 0.1W ±100ppm/°C Molded SMD Punched Carrier T/R")
      (fields
        (field (name "MANUFACTURER") "Panasonic")
        (field (name "MANUFACTURER PART NUMBER") "ERJ-2RKF2400X")
      )
      (libsource (lib "MAX227") (part "ERJ-2RKF2400X"))
    )
    (comp (ref "R28")
      (value "750 ohm")
      (footprint "Resistor-26.7")
      (description "Res Thin Film 0402 750 Ohm 0.1% 0.063W(1/16W) ±10ppm/C Pad SMD Automotive T/R")
      (fields
        (field (name "MANUFACTURER") "Panasonic")
        (field (name "MANUFACTURER PART NUMBER") "ERA-2ARB751X")
      )
      (libsource (lib "MAX227") (part "ERA-2ARB751X"))
    )
    (comp (ref "R29")
      (value "240")
      (footprint "Resistor-26.7")
      (description "Res Thick Film 0402 240 Ohm 1% 0.1W ±100ppm/°C Molded SMD Punched Carrier T/R")
      (fields
        (field (name "MANUFACTURER") "Panasonic")
        (field (name "MANUFACTURER PART NUMBER") "ERJ-2RKF2400X")
      )
      (libsource (lib "MAX227") (part "ERJ-2RKF2400X"))
    )
    (comp (ref "R30")
      (value "10k")
      (footprint "R0805")
      (description "Res Metal Foil 2917 10K Ohm 0.01% 3/5W 2ppm/C Molded SMD T/R - Custom Tape W/Lea")
      (fields
        (field (name "MANUFACTURER") "VPG Foil Resistors")
        (field (name "MANUFACTURER PART NUMBER") "Y116910K0000T9R")
      )
      (libsource (lib "MAX227") (part "Y116910K0000T9R"))
    )
    (comp (ref "R31")
      (value "10k")
      (footprint "R0805")
      (description "Res Metal Foil 2917 10K Ohm 0.01% 3/5W 2ppm/C Molded SMD T/R - Custom Tape W/Lea")
      (fields
        (field (name "MANUFACTURER") "VPG Foil Resistors")
        (field (name "MANUFACTURER PART NUMBER") "Y116910K0000T9R")
      )
      (libsource (lib "MAX227") (part "Y116910K0000T9R"))
    )
    (comp (ref "R32")
      (value "10k")
      (footprint "R0805")
      (description "Res Metal Foil 2917 10K Ohm 0.01% 3/5W 2ppm/C Molded SMD T/R - Custom Tape W/Lea")
      (fields
        (field (name "MANUFACTURER") "VPG Foil Resistors")
        (field (name "MANUFACTURER PART NUMBER") "Y116910K0000T9R")
      )
      (libsource (lib "MAX227") (part "Y116910K0000T9R"))
    )
    (comp (ref "R33")
      (value "0 ohm")
      (footprint "Resistor-26.7")
      (description "GENERAL PURPOSE CHIP RESISTOR Metal Glaze/thick Film, 0.0625W, 0ohm, Surface Mount, 0402")
      (fields
        (field (name "MANUFACTURER") "Yageo Group")
        (field (name "MANUFACTURER PART NUMBER") "RC0402JR-070RL")
      )
      (libsource (lib "MAX227") (part "RC0402JR-070RL"))
    )
    (comp (ref "R34")
      (value "10k")
      (footprint "R0805")
      (description "Res Metal Foil 2917 10K Ohm 0.01% 3/5W 2ppm/C Molded SMD T/R - Custom Tape W/Lea")
      (fields
        (field (name "MANUFACTURER") "VPG Foil Resistors")
        (field (name "MANUFACTURER PART NUMBER") "Y116910K0000T9R")
      )
      (libsource (lib "MAX227") (part "Y116910K0000T9R"))
    )
    (comp (ref "R35")
      (value "0 ohm")
      (footprint "Resistor-26.7")
      (description "GENERAL PURPOSE CHIP RESISTOR Metal Glaze/thick Film, 0.0625W, 0ohm, Surface Mount, 0402")
      (fields
        (field (name "MANUFACTURER") "Yageo Group")
        (field (name "MANUFACTURER PART NUMBER") "RC0402JR-070RL")
      )
      (libsource (lib "MAX227") (part "RC0402JR-070RL"))
    )
    (comp (ref "R36")
      (value "0 ohm")
      (footprint "Resistor-26.7")
      (description "GENERAL PURPOSE CHIP RESISTOR Metal Glaze/thick Film, 0.0625W, 0ohm, Surface Mount, 0402")
      (fields
        (field (name "MANUFACTURER") "Yageo Group")
        (field (name "MANUFACTURER PART NUMBER") "RC0402JR-070RL")
      )
      (libsource (lib "MAX227") (part "RC0402JR-070RL"))
    )
    (comp (ref "R37")
      (value "0 ohm")
      (footprint "Resistor-26.7")
      (description "GENERAL PURPOSE CHIP RESISTOR Metal Glaze/thick Film, 0.0625W, 0ohm, Surface Mount, 0402")
      (fields
        (field (name "MANUFACTURER") "Yageo Group")
        (field (name "MANUFACTURER PART NUMBER") "RC0402JR-070RL")
      )
      (libsource (lib "MAX227") (part "RC0402JR-070RL"))
    )
    (comp (ref "R38")
      (value "0 ohm")
      (footprint "Resistor-26.7")
      (description "GENERAL PURPOSE CHIP RESISTOR Metal Glaze/thick Film, 0.0625W, 0ohm, Surface Mount, 0402")
      (fields
        (field (name "MANUFACTURER") "Yageo Group")
        (field (name "MANUFACTURER PART NUMBER") "RC0402JR-070RL")
      )
      (libsource (lib "MAX227") (part "RC0402JR-070RL"))
    )
    (comp (ref "R39")
      (value "0 ohm")
      (footprint "Resistor-26.7")
      (description "GENERAL PURPOSE CHIP RESISTOR Metal Glaze/thick Film, 0.0625W, 0ohm, Surface Mount, 0402")
      (fields
        (field (name "MANUFACTURER") "Yageo Group")
        (field (name "MANUFACTURER PART NUMBER") "RC0402JR-070RL")
      )
      (libsource (lib "MAX227") (part "RC0402JR-070RL"))
    )
    (comp (ref "R40")
      (value "470k")
      (footprint "Resistor-26.7")
      (description "62.5mW Thick Film Resistors 50V ±100ppm/℃ ±1% 470kΩ 0402 Chip Resistor - Surface Mount ROHS")
      (fields
        (field (name "MANUFACTURER") "Yageo Group")
        (field (name "MANUFACTURER PART NUMBER") "RC0402FR-07470KL")
      )
      (libsource (lib "MAX227") (part "RC0402FR-07470KL"))
    )
    (comp (ref "T1")
      (value "Testpoint")
      (footprint "Testpoints")
      (description "Holes to test various points in the shcematic")
      (libsource (lib "MAX227") (part "Testpoint"))
    )
    (comp (ref "T2")
      (value "Testpoint")
      (footprint "Testpoints")
      (description "Holes to test various points in the shcematic")
      (libsource (lib "MAX227") (part "Testpoint"))
    )
    (comp (ref "T15")
      (value "Testpoint")
      (footprint "Testpoints")
      (description "Holes to test various points in the shcematic")
      (libsource (lib "MAX227") (part "Testpoint"))
    )
    (comp (ref "U1")
      (value "AND GATE IC")
      (footprint "ANDLOGICIC")
      (description "AND CD4081 EAR99 4000B logic gate circuit 90ns @ 15V 50pF 2mm 3.4mA 3.4mA 3.5V-11V")
      (fields
        (field (name "MANUFACTURER") "Texas Instruments")
        (field (name "MANUFACTURER PART NUMBER") "CD4081BNSR")
      )
      (libsource (lib "MAX227") (part "CD4081BNSR"))
    )
    (comp (ref "U2")
      (value "MAX22700EASA+")
      (footprint "MAX227")
      (description "MOSFET and Power Driver 5.7A Single Hi/Lo Side Inv/Non-Inv 8-Pin SOIC N")
      (fields (field (name "MANUFACTURER") "Analog Devices"))
      (libsource (lib "MAX227") (part "MAX22700EASA+"))
    )
    (comp (ref "U3")
      (value "MAX22700EASA+")
      (footprint "MAX227")
      (description "MOSFET and Power Driver 5.7A Single Hi/Lo Side Inv/Non-Inv 8-Pin SOIC N")
      (fields (field (name "MANUFACTURER") "Analog Devices"))
      (libsource (lib "") (part "MAX22700EASA+_1"))
    )
    (comp (ref "U4")
      (value "LTC6240")
      (footprint "LTC6240")
      (description "Single 18MHz, Low Noise, Rail-to-Rail Output, CMOS Op Amp")
      (fields
        (field (name "MANUFACTURER") "Analog Devices")
        (field (name "MANUFACTURER PART NUMBER") "LTC6240HVCS5#TRPBF")
      )
      (libsource (lib "MAX227") (part "LTC6240HVCS5#TRPBF"))
    )
    (comp (ref "U5")
      (value "LTC6240")
      (footprint "LTC6240")
      (description "Single 18MHz, Low Noise, Rail-to-Rail Output, CMOS Op Amp")
      (fields
        (field (name "MANUFACTURER") "Analog Devices")
        (field (name "MANUFACTURER PART NUMBER") "LTC6240HVCS5#TRPBF")
      )
      (libsource (lib "MAX227") (part "LTC6240HVCS5#TRPBF"))
    )
    (comp (ref "U6")
      (value "LT1711")
      (footprint "LT1711")
      (description "Comparator, 1 Func, 6000uV Offset-Max, 5.5ns Response Time, PDSO8")
      (fields
        (field (name "MANUFACTURER") "Analog Devices")
        (field (name "MANUFACTURER PART NUMBER") "LT1711CMS8#TRPBF")
      )
      (libsource (lib "MAX227") (part "LT1711CMS8#TRPBF"))
    )
    (comp (ref "U7")
      (value "MAX22700EASA+")
      (footprint "MAX227")
      (description "MOSFET and Power Driver 5.7A Single Hi/Lo Side Inv/Non-Inv 8-Pin SOIC N")
      (fields (field (name "MANUFACTURER") "Analog Devices"))
      (libsource (lib "MAX227") (part "MAX22700EASA+"))
    )
    (comp (ref "U8")
      (value "MAX22700EASA+")
      (footprint "MAX227")
      (description "MOSFET and Power Driver 5.7A Single Hi/Lo Side Inv/Non-Inv 8-Pin SOIC N")
      (fields (field (name "MANUFACTURER") "Analog Devices"))
      (libsource (lib "") (part "MAX22700EASA+_1"))
    )
    (comp (ref "U9")
      (value "LTC6240")
      (footprint "LTC6240")
      (description "Single 18MHz, Low Noise, Rail-to-Rail Output, CMOS Op Amp")
      (fields
        (field (name "MANUFACTURER") "Analog Devices")
        (field (name "MANUFACTURER PART NUMBER") "LTC6240HVCS5#TRPBF")
      )
      (libsource (lib "MAX227") (part "LTC6240HVCS5#TRPBF"))
    )
    (comp (ref "U10")
      (value "LTC6240")
      (footprint "LTC6240")
      (description "Single 18MHz, Low Noise, Rail-to-Rail Output, CMOS Op Amp")
      (fields
        (field (name "MANUFACTURER") "Analog Devices")
        (field (name "MANUFACTURER PART NUMBER") "LTC6240HVCS5#TRPBF")
      )
      (libsource (lib "MAX227") (part "LTC6240HVCS5#TRPBF"))
    )
    (comp (ref "U11")
      (value "LT1711")
      (footprint "LT1711")
      (description "Comparator, 1 Func, 6000uV Offset-Max, 5.5ns Response Time, PDSO8")
      (fields
        (field (name "MANUFACTURER") "Analog Devices")
        (field (name "MANUFACTURER PART NUMBER") "LT1711CMS8#TRPBF")
      )
      (libsource (lib "MAX227") (part "LT1711CMS8#TRPBF"))
    )
    (comp (ref "U12")
      (value "AND GATE IC")
      (footprint "ANDLOGICIC")
      (description "AND CD4081 EAR99 4000B logic gate circuit 90ns @ 15V 50pF 2mm 3.4mA 3.4mA 3.5V-11V")
      (fields
        (field (name "MANUFACTURER") "Texas Instruments")
        (field (name "MANUFACTURER PART NUMBER") "CD4081BNSR")
      )
      (libsource (lib "MAX227") (part "CD4081BNSR"))
    )
    (comp (ref "U13")
      (value "LTC6240")
      (footprint "LTC6240")
      (description "Single 18MHz, Low Noise, Rail-to-Rail Output, CMOS Op Amp")
      (fields
        (field (name "MANUFACTURER") "Analog Devices")
        (field (name "MANUFACTURER PART NUMBER") "LTC6240HVCS5#TRPBF")
      )
      (libsource (lib "") (part "LTC6240HVCS5#TRPBF_1"))
    )
    (comp (ref "U14")
      (value "LTC6240")
      (footprint "LTC6240")
      (description "Single 18MHz, Low Noise, Rail-to-Rail Output, CMOS Op Amp")
      (fields
        (field (name "MANUFACTURER") "Analog Devices")
        (field (name "MANUFACTURER PART NUMBER") "LTC6240HVCS5#TRPBF")
      )
      (libsource (lib "") (part "LTC6240HVCS5#TRPBF_1"))
    )
    (comp (ref "U15")
      (value "LTC6240")
      (footprint "LTC6240")
      (description "Single 18MHz, Low Noise, Rail-to-Rail Output, CMOS Op Amp")
      (fields
        (field (name "MANUFACTURER") "Analog Devices")
        (field (name "MANUFACTURER PART NUMBER") "LTC6240HVCS5#TRPBF")
      )
      (libsource (lib "MAX227") (part "LTC6240HVCS5#TRPBF"))
    )
    (comp (ref "U16")
      (value "LTC6240")
      (footprint "LTC6240")
      (description "Single 18MHz, Low Noise, Rail-to-Rail Output, CMOS Op Amp")
      (fields
        (field (name "MANUFACTURER") "Analog Devices")
        (field (name "MANUFACTURER PART NUMBER") "LTC6240HVCS5#TRPBF")
      )
      (libsource (lib "MAX227") (part "LTC6240HVCS5#TRPBF"))
    )
    (comp (ref "U17")
      (value "Voltage Regulator")
      (footprint "SOT254P700X939-4N")
      (description "LDO Regulator Pos 1.5A 3-Pin(3+Tab) TO-220")
      (fields
        (field (name "MANUFACTURER") "Analog Devices")
        (field (name "MANUFACTURER PART NUMBER") "LT317AT#PBF")
      )
      (libsource (lib "MAX227") (part "LT317AT#PBF"))
    )
    (comp (ref "U18")
      (value "Voltage Regulator")
      (footprint "SOT254P700X939-4N")
      (description "LDO Regulator Pos 1.5A 3-Pin(3+Tab) TO-220")
      (fields
        (field (name "MANUFACTURER") "Analog Devices")
        (field (name "MANUFACTURER PART NUMBER") "LT317AT#PBF")
      )
      (libsource (lib "MAX227") (part "LT317AT#PBF"))
    )
  )
  (nets
    (net (code "1") (name "+2.5V") (class "Default")
      (node (ref "C11") (pin "2") (pinfunction "2_2") (pintype "passive"))
      (node (ref "C57") (pin "1") (pinfunction "1_1") (pintype "passive"))
      (node (ref "R27") (pin "2") (pinfunction "2_2") (pintype "passive"))
      (node (ref "R30") (pin "1") (pinfunction "1_1") (pintype "passive"))
      (node (ref "R31") (pin "2") (pinfunction "2_2") (pintype "passive"))
      (node (ref "R32") (pin "2") (pinfunction "2_2") (pintype "passive"))
      (node (ref "R34") (pin "2") (pinfunction "2_2") (pintype "passive"))
      (node (ref "T1") (pin "T") (pinfunction "T_T") (pintype "passive"))
      (node (ref "U18") (pin "3") (pinfunction "Vout_3") (pintype "passive"))
    )
    (net (code "2") (name "+5V") (class "Default")
      (node (ref "C10") (pin "1") (pinfunction "1_1") (pintype "passive"))
      (node (ref "C13") (pin "1") (pinfunction "1_1") (pintype "passive"))
      (node (ref "C14") (pin "2") (pinfunction "2_2") (pintype "passive"))
      (node (ref "C15") (pin "2") (pinfunction "2_2") (pintype "passive"))
      (node (ref "C16") (pin "2") (pinfunction "2_2") (pintype "passive"))
      (node (ref "C17") (pin "2") (pinfunction "2_2") (pintype "passive"))
      (node (ref "C18") (pin "1") (pinfunction "1_1") (pintype "passive"))
      (node (ref "C19") (pin "1") (pinfunction "1_1") (pintype "passive"))
      (node (ref "C20") (pin "1") (pinfunction "1_1") (pintype "passive"))
      (node (ref "C21") (pin "1") (pinfunction "1_1") (pintype "passive"))
      (node (ref "C22") (pin "1") (pinfunction "1_1") (pintype "passive"))
      (node (ref "C23") (pin "1") (pinfunction "1_1") (pintype "passive"))
      (node (ref "C24") (pin "2") (pinfunction "2_2") (pintype "passive"))
      (node (ref "C25") (pin "1") (pinfunction "1_1") (pintype "passive"))
      (node (ref "C26") (pin "1") (pinfunction "1_1") (pintype "passive"))
      (node (ref "C27") (pin "1") (pinfunction "1_1") (pintype "passive"))
      (node (ref "C31") (pin "2") (pinfunction "2_2") (pintype "passive"))
      (node (ref "C38") (pin "1") (pinfunction "1_1") (pintype "passive"))
      (node (ref "C44") (pin "2") (pinfunction "2_2") (pintype "passive"))
      (node (ref "C46") (pin "2") (pinfunction "2_2") (pintype "passive"))
      (node (ref "C47") (pin "2") (pinfunction "2_2") (pintype "passive"))
      (node (ref "C48") (pin "2") (pinfunction "2_2") (pintype "passive"))
      (node (ref "C50") (pin "2") (pinfunction "2_2") (pintype "passive"))
      (node (ref "C7") (pin "2") (pinfunction "2_2") (pintype "passive"))
      (node (ref "C8") (pin "2") (pinfunction "2_2") (pintype "passive"))
      (node (ref "C9") (pin "2") (pinfunction "2_2") (pintype "passive"))
      (node (ref "R26") (pin "2") (pinfunction "2_2") (pintype "passive"))
      (node (ref "T2") (pin "T") (pinfunction "T_T") (pintype "passive"))
      (node (ref "U1") (pin "14") (pinfunction "VDD_14") (pintype "passive"))
      (node (ref "U10") (pin "5") (pinfunction "V+_5") (pintype "passive"))
      (node (ref "U11") (pin "1") (pinfunction "V+_1") (pintype "passive"))
      (node (ref "U12") (pin "14") (pinfunction "VDD_14") (pintype "passive"))
      (node (ref "U13") (pin "5") (pinfunction "V+_5") (pintype "passive"))
      (node (ref "U14") (pin "5") (pinfunction "V+_5") (pintype "passive"))
      (node (ref "U15") (pin "5") (pinfunction "V+_5") (pintype "passive"))
      (node (ref "U16") (pin "5") (pinfunction "V+_5") (pintype "passive"))
      (node (ref "U17") (pin "3") (pinfunction "Vout_3") (pintype "passive"))
      (node (ref "U18") (pin "1") (pinfunction "Vin_1") (pintype "passive"))
      (node (ref "U2") (pin "1") (pinfunction "VDDA_1") (pintype "passive"))
      (node (ref "U3") (pin "1") (pinfunction "VDDA_1") (pintype "passive"))
      (node (ref "U4") (pin "5") (pinfunction "V+_5") (pintype "passive"))
      (node (ref "U5") (pin "5") (pinfunction "V+_5") (pintype "passive"))
      (node (ref "U6") (pin "1") (pinfunction "V+_1") (pintype "passive"))
      (node (ref "U7") (pin "1") (pinfunction "VDDA_1") (pintype "passive"))
      (node (ref "U8") (pin "1") (pinfunction "VDDA_1") (pintype "passive"))
      (node (ref "U9") (pin "5") (pinfunction "V+_5") (pintype "passive"))
    )
    (net (code "3") (name "+20V") (class "Default")
      (node (ref "C12") (pin "1") (pinfunction "1_1") (pintype "passive"))
      (node (ref "C34") (pin "2") (pinfunction "2_2") (pintype "passive"))
      (node (ref "C36") (pin "2") (pinfunction "2_2") (pintype "passive"))
      (node (ref "C51") (pin "2") (pinfunction "2_2") (pintype "passive"))
      (node (ref "C52") (pin "2") (pinfunction "2_2") (pintype "passive"))
      (node (ref "C53") (pin "2") (pinfunction "2_2") (pintype "passive"))
      (node (ref "C55") (pin "2") (pinfunction "2_2") (pintype "passive"))
      (node (ref "C56") (pin "2") (pinfunction "2_2") (pintype "passive"))
      (node (ref "C58") (pin "2") (pinfunction "2_2") (pintype "passive"))
      (node (ref "P2") (pin "1") (pinfunction "1_1") (pintype "passive"))
      (node (ref "U17") (pin "1") (pinfunction "Vin_1") (pintype "passive"))
      (node (ref "U7") (pin "8") (pinfunction "VDDB_8") (pintype "passive"))
      (node (ref "U8") (pin "8") (pinfunction "VDDB_8") (pintype "passive"))
    )
    (net (code "4") (name "+20V_1") (class "Default")
      (node (ref "C28") (pin "2") (pinfunction "2_2") (pintype "passive"))
      (node (ref "C3") (pin "2") (pinfunction "2_2") (pintype "passive"))
      (node (ref "C30") (pin "2") (pinfunction "2_2") (pintype "passive"))
      (node (ref "C32") (pin "2") (pinfunction "2_2") (pintype "passive"))
      (node (ref "P7") (pin "1") (pinfunction "1_1") (pintype "passive"))
      (node (ref "U2") (pin "8") (pinfunction "VDDB_8") (pintype "passive"))
    )
    (net (code "5") (name "+20V_2") (class "Default")
      (node (ref "C29") (pin "2") (pinfunction "2_2") (pintype "passive"))
      (node (ref "C33") (pin "2") (pinfunction "2_2") (pintype "passive"))
      (node (ref "C35") (pin "2") (pinfunction "2_2") (pintype "passive"))
      (node (ref "C6") (pin "2") (pinfunction "2_2") (pintype "passive"))
      (node (ref "P8") (pin "1") (pinfunction "1_1") (pintype "passive"))
      (node (ref "U3") (pin "8") (pinfunction "VDDB_8") (pintype "passive"))
    )
    (net (code "6") (name "+170") (class "Default")
      (node (ref "M1") (pin "Drain") (pinfunction "Drain_Drain") (pintype "passive"))
      (node (ref "M2") (pin "Drain") (pinfunction "Drain_Drain") (pintype "passive"))
      (node (ref "P1") (pin "1") (pinfunction "1_1") (pintype "passive"))
    )
    (net (code "7") (name "-20V_1") (class "Default")
      (node (ref "C28") (pin "1") (pinfunction "1_1") (pintype "passive"))
      (node (ref "C3") (pin "1") (pinfunction "1_1") (pintype "passive"))
      (node (ref "C30") (pin "1") (pinfunction "1_1") (pintype "passive"))
      (node (ref "C32") (pin "1") (pinfunction "1_1") (pintype "passive"))
      (node (ref "P9") (pin "1") (pinfunction "1_1") (pintype "passive"))
      (node (ref "U2") (pin "6") (pinfunction "VSSB_6") (pintype "passive"))
    )
    (net (code "8") (name "-20V_2") (class "Default")
      (node (ref "C29") (pin "1") (pinfunction "1_1") (pintype "passive"))
      (node (ref "C33") (pin "1") (pinfunction "1_1") (pintype "passive"))
      (node (ref "C35") (pin "1") (pinfunction "1_1") (pintype "passive"))
      (node (ref "C6") (pin "1") (pinfunction "1_1") (pintype "passive"))
      (node (ref "P10") (pin "1") (pinfunction "1_1") (pintype "passive"))
      (node (ref "U3") (pin "6") (pinfunction "VSSB_6") (pintype "passive"))
    )
    (net (code "9") (name "GND") (class "Default")
      (node (ref "C1") (pin "2") (pinfunction "2_2") (pintype "passive"))
      (node (ref "C10") (pin "2") (pinfunction "2_2") (pintype "passive"))
      (node (ref "C11") (pin "1") (pinfunction "1_1") (pintype "passive"))
      (node (ref "C12") (pin "2") (pinfunction "2_2") (pintype "passive"))
      (node (ref "C13") (pin "2") (pinfunction "2_2") (pintype "passive"))
      (node (ref "C14") (pin "1") (pinfunction "1_1") (pintype "passive"))
      (node (ref "C15") (pin "1") (pinfunction "1_1") (pintype "passive"))
      (node (ref "C16") (pin "1") (pinfunction "1_1") (pintype "passive"))
      (node (ref "C17") (pin "1") (pinfunction "1_1") (pintype "passive"))
      (node (ref "C18") (pin "2") (pinfunction "2_2") (pintype "passive"))
      (node (ref "C19") (pin "2") (pinfunction "2_2") (pintype "passive"))
      (node (ref "C2") (pin "1") (pinfunction "1_1") (pintype "passive"))
      (node (ref "C20") (pin "2") (pinfunction "2_2") (pintype "passive"))
      (node (ref "C21") (pin "2") (pinfunction "2_2") (pintype "passive"))
      (node (ref "C22") (pin "2") (pinfunction "2_2") (pintype "passive"))
      (node (ref "C23") (pin "2") (pinfunction "2_2") (pintype "passive"))
      (node (ref "C24") (pin "1") (pinfunction "1_1") (pintype "passive"))
      (node (ref "C25") (pin "2") (pinfunction "2_2") (pintype "passive"))
      (node (ref "C26") (pin "2") (pinfunction "2_2") (pintype "passive"))
      (node (ref "C27") (pin "2") (pinfunction "2_2") (pintype "passive"))
      (node (ref "C31") (pin "1") (pinfunction "1_1") (pintype "passive"))
      (node (ref "C34") (pin "1") (pinfunction "1_1") (pintype "passive"))
      (node (ref "C36") (pin "1") (pinfunction "1_1") (pintype "passive"))
      (node (ref "C37") (pin "1") (pinfunction "1_1") (pintype "passive"))
      (node (ref "C38") (pin "2") (pinfunction "2_2") (pintype "passive"))
      (node (ref "C39") (pin "2") (pinfunction "2_2") (pintype "passive"))
      (node (ref "C4") (pin "2") (pinfunction "2_2") (pintype "passive"))
      (node (ref "C40") (pin "1") (pinfunction "1_1") (pintype "passive"))
      (node (ref "C41") (pin "2") (pinfunction "2_2") (pintype "passive"))
      (node (ref "C42") (pin "1") (pinfunction "1_1") (pintype "passive"))
      (node (ref "C43") (pin "1") (pinfunction "1_1") (pintype "passive"))
      (node (ref "C44") (pin "1") (pinfunction "1_1") (pintype "passive"))
      (node (ref "C45") (pin "1") (pinfunction "1_1") (pintype "passive"))
      (node (ref "C46") (pin "1") (pinfunction "1_1") (pintype "passive"))
      (node (ref "C47") (pin "1") (pinfunction "1_1") (pintype "passive"))
      (node (ref "C48") (pin "1") (pinfunction "1_1") (pintype "passive"))
      (node (ref "C49") (pin "1") (pinfunction "1_1") (pintype "passive"))
      (node (ref "C5") (pin "2") (pinfunction "2_2") (pintype "passive"))
      (node (ref "C50") (pin "1") (pinfunction "1_1") (pintype "passive"))
      (node (ref "C51") (pin "1") (pinfunction "1_1") (pintype "passive"))
      (node (ref "C52") (pin "1") (pinfunction "1_1") (pintype "passive"))
      (node (ref "C53") (pin "1") (pinfunction "1_1") (pintype "passive"))
      (node (ref "C55") (pin "1") (pinfunction "1_1") (pintype "passive"))
      (node (ref "C56") (pin "1") (pinfunction "1_1") (pintype "passive"))
      (node (ref "C57") (pin "2") (pinfunction "2_2") (pintype "passive"))
      (node (ref "C58") (pin "1") (pinfunction "1_1") (pintype "passive"))
      (node (ref "C7") (pin "1") (pinfunction "1_1") (pintype "passive"))
      (node (ref "C8") (pin "1") (pinfunction "1_1") (pintype "passive"))
      (node (ref "C9") (pin "1") (pinfunction "1_1") (pintype "passive"))
      (node (ref "M3") (pin "Source") (pinfunction "Source_Source") (pintype "passive"))
      (node (ref "M4") (pin "Source") (pinfunction "Source_Source") (pintype "passive"))
      (node (ref "P5") (pin "1") (pinfunction "1_1") (pintype "passive"))
      (node (ref "P6") (pin "1") (pinfunction "1_1") (pintype "passive"))
      (node (ref "R1") (pin "2") (pinfunction "2_2") (pintype "passive"))
      (node (ref "R19") (pin "2") (pinfunction "2_2") (pintype "passive"))
      (node (ref "R20") (pin "1") (pinfunction "1_1") (pintype "passive"))
      (node (ref "R21") (pin "2") (pinfunction "2_2") (pintype "passive"))
      (node (ref "R22") (pin "2") (pinfunction "2_2") (pintype "passive"))
      (node (ref "R23") (pin "1") (pinfunction "1_1") (pintype "passive"))
      (node (ref "R24") (pin "2") (pinfunction "2_2") (pintype "passive"))
      (node (ref "R28") (pin "1") (pinfunction "1_1") (pintype "passive"))
      (node (ref "R29") (pin "1") (pinfunction "1_1") (pintype "passive"))
      (node (ref "R33") (pin "1") (pinfunction "1_1") (pintype "passive"))
      (node (ref "R35") (pin "2") (pinfunction "2_2") (pintype "passive"))
      (node (ref "U1") (pin "7") (pinfunction "VSS_7") (pintype "passive"))
      (node (ref "U10") (pin "2") (pinfunction "V-_2") (pintype "passive"))
      (node (ref "U11") (pin "6") (pinfunction "GND_6") (pintype "passive"))
      (node (ref "U12") (pin "7") (pinfunction "VSS_7") (pintype "passive"))
      (node (ref "U13") (pin "2") (pinfunction "V-_2") (pintype "passive"))
      (node (ref "U14") (pin "2") (pinfunction "V-_2") (pintype "passive"))
      (node (ref "U15") (pin "2") (pinfunction "V-_2") (pintype "passive"))
      (node (ref "U16") (pin "2") (pinfunction "V-_2") (pintype "passive"))
      (node (ref "U2") (pin "4") (pinfunction "GNDA_4") (pintype "passive"))
      (node (ref "U3") (pin "4") (pinfunction "GNDA_4") (pintype "passive"))
      (node (ref "U4") (pin "2") (pinfunction "V-_2") (pintype "passive"))
      (node (ref "U5") (pin "2") (pinfunction "V-_2") (pintype "passive"))
      (node (ref "U6") (pin "6") (pinfunction "GND_6") (pintype "passive"))
      (node (ref "U7") (pin "4") (pinfunction "GNDA_4") (pintype "passive"))
      (node (ref "U7") (pin "5") (pinfunction "GNDB_5") (pintype "passive"))
      (node (ref "U7") (pin "6") (pinfunction "VSSB_6") (pintype "passive"))
      (node (ref "U8") (pin "4") (pinfunction "GNDA_4") (pintype "passive"))
      (node (ref "U8") (pin "5") (pinfunction "GNDB_5") (pintype "passive"))
      (node (ref "U8") (pin "6") (pinfunction "VSSB_6") (pintype "passive"))
      (node (ref "U9") (pin "2") (pinfunction "V-_2") (pintype "passive"))
    )
    (net (code "10") (name "Net-(C45-Pad2)") (class "Default")
      (node (ref "C45") (pin "2") (pinfunction "2_2") (pintype "passive"))
      (node (ref "R40") (pin "1") (pinfunction "1_1") (pintype "passive"))
      (node (ref "R9") (pin "1") (pinfunction "1_1") (pintype "passive"))
    )
    (net (code "11") (name "Net-(M1-PadGate)") (class "Default")
      (node (ref "M1") (pin "Gate") (pinfunction "Gate_Gate") (pintype "passive"))
      (node (ref "R15") (pin "1") (pinfunction "1_1") (pintype "passive"))
    )
    (net (code "12") (name "Net-(M2-PadGate)") (class "Default")
      (node (ref "M2") (pin "Gate") (pinfunction "Gate_Gate") (pintype "passive"))
      (node (ref "R16") (pin "2") (pinfunction "2_2") (pintype "passive"))
    )
    (net (code "13") (name "Net-(M3-PadGate)") (class "Default")
      (node (ref "M3") (pin "Gate") (pinfunction "Gate_Gate") (pintype "passive"))
      (node (ref "R17") (pin "1") (pinfunction "1_1") (pintype "passive"))
    )
    (net (code "14") (name "Net-(M4-PadGate)") (class "Default")
      (node (ref "M4") (pin "Gate") (pinfunction "Gate_Gate") (pintype "passive"))
      (node (ref "R18") (pin "2") (pinfunction "2_2") (pintype "passive"))
    )
    (net (code "15") (name "Net-(U1-A)") (class "Default")
      (node (ref "C1") (pin "1") (pinfunction "1_1") (pintype "passive"))
      (node (ref "R36") (pin "1") (pinfunction "1_1") (pintype "passive"))
      (node (ref "U1") (pin "1") (pinfunction "A_1") (pintype "passive"))
    )
    (net (code "16") (name "Net-(U1-B)") (class "Default")
      (node (ref "R36") (pin "2") (pinfunction "2_2") (pintype "passive"))
      (node (ref "U1") (pin "2") (pinfunction "B_2") (pintype "passive"))
      (node (ref "U6") (pin "7") (pinfunction "Q_7") (pintype "passive"))
    )
    (net (code "17") (name "Net-(U1-E)") (class "Default")
      (node (ref "R37") (pin "2") (pinfunction "2_2") (pintype "passive"))
      (node (ref "U1") (pin "8") (pinfunction "E_8") (pintype "passive"))
      (node (ref "U6") (pin "8") (pinfunction "~{Q}_8") (pintype "passive"))
    )
    (net (code "18") (name "Net-(U1-F)") (class "Default")
      (node (ref "C2") (pin "2") (pinfunction "2_2") (pintype "passive"))
      (node (ref "R37") (pin "1") (pinfunction "1_1") (pintype "passive"))
      (node (ref "U1") (pin "9") (pinfunction "F_9") (pintype "passive"))
    )
    (net (code "19") (name "Net-(U1-K)") (class "Default")
      (node (ref "R6") (pin "1") (pinfunction "1_1") (pintype "passive"))
      (node (ref "U1") (pin "4") (pinfunction "K_4") (pintype "passive"))
    )
    (net (code "20") (name "Net-(U1-M)") (class "Default")
      (node (ref "R2") (pin "1") (pinfunction "1_1") (pintype "passive"))
      (node (ref "U1") (pin "11") (pinfunction "M_11") (pintype "passive"))
    )
    (net (code "21") (name "Net-(U2-GNDB)") (class "Default")
      (node (ref "M1") (pin "Source") (pinfunction "Source_Source") (pintype "passive"))
      (node (ref "M3") (pin "Drain") (pinfunction "Drain_Drain") (pintype "passive"))
      (node (ref "P3") (pin "1") (pinfunction "1_1") (pintype "passive"))
      (node (ref "U2") (pin "5") (pinfunction "GNDB_5") (pintype "passive"))
    )
    (net (code "22") (name "Net-(U2-IN)") (class "Default")
      (node (ref "R2") (pin "2") (pinfunction "2_2") (pintype "passive"))
      (node (ref "U2") (pin "2") (pinfunction "IN_2") (pintype "passive"))
    )
    (net (code "23") (name "Net-(U2-OUT)") (class "Default")
      (node (ref "R15") (pin "2") (pinfunction "2_2") (pintype "passive"))
      (node (ref "U2") (pin "7") (pinfunction "OUT_7") (pintype "passive"))
    )
    (net (code "24") (name "Net-(U2-~{EN})") (class "Default")
      (node (ref "R19") (pin "1") (pinfunction "1_1") (pintype "passive"))
      (node (ref "U2") (pin "3") (pinfunction "~{EN}_3") (pintype "passive"))
    )
    (net (code "25") (name "Net-(U3-GNDB)") (class "Default")
      (node (ref "M2") (pin "Source") (pinfunction "Source_Source") (pintype "passive"))
      (node (ref "M4") (pin "Drain") (pinfunction "Drain_Drain") (pintype "passive"))
      (node (ref "P4") (pin "1") (pinfunction "1_1") (pintype "passive"))
      (node (ref "U3") (pin "5") (pinfunction "GNDB_5") (pintype "passive"))
    )
    (net (code "26") (name "Net-(U3-IN)") (class "Default")
      (node (ref "R13") (pin "1") (pinfunction "1_1") (pintype "passive"))
      (node (ref "U3") (pin "2") (pinfunction "IN_2") (pintype "passive"))
    )
    (net (code "27") (name "Net-(U3-OUT)") (class "Default")
      (node (ref "R16") (pin "1") (pinfunction "1_1") (pintype "passive"))
      (node (ref "U3") (pin "7") (pinfunction "OUT_7") (pintype "passive"))
    )
    (net (code "28") (name "Net-(U3-~{EN})") (class "Default")
      (node (ref "R20") (pin "2") (pinfunction "2_2") (pintype "passive"))
      (node (ref "U3") (pin "3") (pinfunction "~{EN}_3") (pintype "passive"))
    )
    (net (code "29") (name "Net-(U4-+IN)") (class "Default")
      (node (ref "R3") (pin "1") (pinfunction "1_1") (pintype "passive"))
      (node (ref "U4") (pin "3") (pinfunction "+IN_3") (pintype "passive"))
    )
    (net (code "30") (name "Net-(U4--IN)") (class "Default")
      (node (ref "C39") (pin "1") (pinfunction "1_1") (pintype "passive"))
      (node (ref "R30") (pin "2") (pinfunction "2_2") (pintype "passive"))
      (node (ref "U4") (pin "4") (pinfunction "-IN_4") (pintype "passive"))
    )
    (net (code "31") (name "Net-(U5-+IN)") (class "Default")
      (node (ref "C40") (pin "2") (pinfunction "2_2") (pintype "passive"))
      (node (ref "R31") (pin "1") (pinfunction "1_1") (pintype "passive"))
      (node (ref "U5") (pin "3") (pinfunction "+IN_3") (pintype "passive"))
    )
    (net (code "32") (name "Net-(U5--IN)") (class "Default")
      (node (ref "C54") (pin "1") (pinfunction "1_1") (pintype "passive"))
      (node (ref "R4") (pin "2") (pinfunction "2_2") (pintype "passive"))
      (node (ref "U5") (pin "4") (pinfunction "-IN_4") (pintype "passive"))
    )
    (net (code "33") (name "Net-(U6-LATCH_EN)") (class "Default")
      (node (ref "R23") (pin "2") (pinfunction "2_2") (pintype "passive"))
      (node (ref "U6") (pin "5") (pinfunction "LATCH_EN_5") (pintype "passive"))
    )
    (net (code "34") (name "Net-(U6-V-)") (class "Default")
      (node (ref "R33") (pin "2") (pinfunction "2_2") (pintype "passive"))
      (node (ref "U6") (pin "4") (pinfunction "V-_4") (pintype "passive"))
    )
    (net (code "35") (name "Net-(U7-IN)") (class "Default")
      (node (ref "R6") (pin "2") (pinfunction "2_2") (pintype "passive"))
      (node (ref "U7") (pin "2") (pinfunction "IN_2") (pintype "passive"))
    )
    (net (code "36") (name "Net-(U7-OUT)") (class "Default")
      (node (ref "R17") (pin "2") (pinfunction "2_2") (pintype "passive"))
      (node (ref "U7") (pin "7") (pinfunction "OUT_7") (pintype "passive"))
    )
    (net (code "37") (name "Net-(U7-~{EN})") (class "Default")
      (node (ref "R22") (pin "1") (pinfunction "1_1") (pintype "passive"))
      (node (ref "U7") (pin "3") (pinfunction "~{EN}_3") (pintype "passive"))
    )
    (net (code "38") (name "Net-(U8-IN)") (class "Default")
      (node (ref "R14") (pin "1") (pinfunction "1_1") (pintype "passive"))
      (node (ref "U8") (pin "2") (pinfunction "IN_2") (pintype "passive"))
    )
    (net (code "39") (name "Net-(U8-OUT)") (class "Default")
      (node (ref "R18") (pin "1") (pinfunction "1_1") (pintype "passive"))
      (node (ref "U8") (pin "7") (pinfunction "OUT_7") (pintype "passive"))
    )
    (net (code "40") (name "Net-(U8-~{EN})") (class "Default")
      (node (ref "R21") (pin "1") (pinfunction "1_1") (pintype "passive"))
      (node (ref "U8") (pin "3") (pinfunction "~{EN}_3") (pintype "passive"))
    )
    (net (code "41") (name "Net-(U9-+IN)") (class "Default")
      (node (ref "C42") (pin "2") (pinfunction "2_2") (pintype "passive"))
      (node (ref "R32") (pin "1") (pinfunction "1_1") (pintype "passive"))
      (node (ref "U9") (pin "3") (pinfunction "+IN_3") (pintype "passive"))
    )
    (net (code "42") (name "Net-(U9--IN)") (class "Default")
      (node (ref "R40") (pin "2") (pinfunction "2_2") (pintype "passive"))
      (node (ref "R5") (pin "1") (pinfunction "1_1") (pintype "passive"))
      (node (ref "U9") (pin "4") (pinfunction "-IN_4") (pintype "passive"))
    )
    (net (code "43") (name "Net-(U9-out)") (class "Default")
      (node (ref "R5") (pin "2") (pinfunction "2_2") (pintype "passive"))
      (node (ref "R7") (pin "1") (pinfunction "1_1") (pintype "passive"))
      (node (ref "U9") (pin "1") (pinfunction "out_1") (pintype "passive"))
    )
    (net (code "44") (name "Net-(U10-+IN)") (class "Default")
      (node (ref "C37") (pin "2") (pinfunction "2_2") (pintype "passive"))
      (node (ref "R7") (pin "2") (pinfunction "2_2") (pintype "passive"))
      (node (ref "U10") (pin "3") (pinfunction "+IN_3") (pintype "passive"))
    )
    (net (code "45") (name "Net-(U10--IN)") (class "Default")
      (node (ref "R8") (pin "2") (pinfunction "2_2") (pintype "passive"))
      (node (ref "U10") (pin "1") (pinfunction "out_1") (pintype "passive"))
      (node (ref "U10") (pin "4") (pinfunction "-IN_4") (pintype "passive"))
    )
    (net (code "46") (name "Net-(U11-+IN)") (class "Default")
      (node (ref "C54") (pin "2") (pinfunction "2_2") (pintype "passive"))
      (node (ref "R1") (pin "1") (pinfunction "1_1") (pintype "passive"))
      (node (ref "R3") (pin "2") (pinfunction "2_2") (pintype "passive"))
      (node (ref "R4") (pin "1") (pinfunction "1_1") (pintype "passive"))
      (node (ref "U11") (pin "2") (pinfunction "+IN_2") (pintype "passive"))
      (node (ref "U4") (pin "1") (pinfunction "out_1") (pintype "passive"))
      (node (ref "U5") (pin "1") (pinfunction "out_1") (pintype "passive"))
      (node (ref "U6") (pin "2") (pinfunction "+IN_2") (pintype "passive"))
    )
    (net (code "47") (name "Net-(U11--IN)") (class "Default")
      (node (ref "R12") (pin "2") (pinfunction "2_2") (pintype "passive"))
      (node (ref "T15") (pin "T") (pinfunction "T_T") (pintype "passive"))
      (node (ref "U11") (pin "3") (pinfunction "-IN_3") (pintype "passive"))
      (node (ref "U16") (pin "1") (pinfunction "out_1") (pintype "passive"))
    )
    (net (code "48") (name "Net-(U11-LATCH_EN)") (class "Default")
      (node (ref "R35") (pin "1") (pinfunction "1_1") (pintype "passive"))
      (node (ref "U11") (pin "5") (pinfunction "LATCH_EN_5") (pintype "passive"))
    )
    (net (code "49") (name "Net-(U11-Q)") (class "Default")
      (node (ref "R39") (pin "2") (pinfunction "2_2") (pintype "passive"))
      (node (ref "U11") (pin "7") (pinfunction "Q_7") (pintype "passive"))
      (node (ref "U12") (pin "13") (pinfunction "H_13") (pintype "passive"))
    )
    (net (code "50") (name "Net-(U11-V-)") (class "Default")
      (node (ref "R24") (pin "1") (pinfunction "1_1") (pintype "passive"))
      (node (ref "U11") (pin "4") (pinfunction "V-_4") (pintype "passive"))
    )
    (net (code "51") (name "Net-(U11-~{Q})") (class "Default")
      (node (ref "R38") (pin "2") (pinfunction "2_2") (pintype "passive"))
      (node (ref "U11") (pin "8") (pinfunction "~{Q}_8") (pintype "passive"))
      (node (ref "U12") (pin "2") (pinfunction "B_2") (pintype "passive"))
    )
    (net (code "52") (name "Net-(U12-A)") (class "Default")
      (node (ref "C4") (pin "1") (pinfunction "1_1") (pintype "passive"))
      (node (ref "R38") (pin "1") (pinfunction "1_1") (pintype "passive"))
      (node (ref "U12") (pin "1") (pinfunction "A_1") (pintype "passive"))
    )
    (net (code "53") (name "Net-(U12-G)") (class "Default")
      (node (ref "C5") (pin "1") (pinfunction "1_1") (pintype "passive"))
      (node (ref "R39") (pin "1") (pinfunction "1_1") (pintype "passive"))
      (node (ref "U12") (pin "12") (pinfunction "G_12") (pintype "passive"))
    )
    (net (code "54") (name "Net-(U12-J)") (class "Default")
      (node (ref "R13") (pin "2") (pinfunction "2_2") (pintype "passive"))
      (node (ref "U12") (pin "3") (pinfunction "J_3") (pintype "passive"))
    )
    (net (code "55") (name "Net-(U12-M)") (class "Default")
      (node (ref "R14") (pin "2") (pinfunction "2_2") (pintype "passive"))
      (node (ref "U12") (pin "11") (pinfunction "M_11") (pintype "passive"))
    )
    (net (code "56") (name "Net-(U13-+IN)") (class "Default")
      (node (ref "C49") (pin "2") (pinfunction "2_2") (pintype "passive"))
      (node (ref "R10") (pin "1") (pinfunction "1_1") (pintype "passive"))
      (node (ref "U13") (pin "3") (pinfunction "+IN_3") (pintype "passive"))
    )
    (net (code "57") (name "Net-(U13--IN)") (class "Default")
      (node (ref "R9") (pin "2") (pinfunction "2_2") (pintype "passive"))
      (node (ref "U13") (pin "1") (pinfunction "out_1") (pintype "passive"))
      (node (ref "U13") (pin "4") (pinfunction "-IN_4") (pintype "passive"))
    )
    (net (code "58") (name "Net-(U14-+IN)") (class "Default")
      (node (ref "C43") (pin "2") (pinfunction "2_2") (pintype "passive"))
      (node (ref "R25") (pin "2") (pinfunction "2_2") (pintype "passive"))
      (node (ref "R8") (pin "1") (pinfunction "1_1") (pintype "passive"))
      (node (ref "U14") (pin "3") (pinfunction "+IN_3") (pintype "passive"))
      (node (ref "U6") (pin "3") (pinfunction "-IN_3") (pintype "passive"))
    )
    (net (code "59") (name "Net-(U14--IN)") (class "Default")
      (node (ref "R10") (pin "2") (pinfunction "2_2") (pintype "passive"))
      (node (ref "U14") (pin "1") (pinfunction "out_1") (pintype "passive"))
      (node (ref "U14") (pin "4") (pinfunction "-IN_4") (pintype "passive"))
    )
    (net (code "60") (name "Net-(U15-+IN)") (class "Default")
      (node (ref "R25") (pin "1") (pinfunction "1_1") (pintype "passive"))
      (node (ref "U15") (pin "3") (pinfunction "+IN_3") (pintype "passive"))
    )
    (net (code "61") (name "Net-(U15--IN)") (class "Default")
      (node (ref "R11") (pin "1") (pinfunction "1_1") (pintype "passive"))
      (node (ref "U15") (pin "1") (pinfunction "out_1") (pintype "passive"))
      (node (ref "U15") (pin "4") (pinfunction "-IN_4") (pintype "passive"))
    )
    (net (code "62") (name "Net-(U16-+IN)") (class "Default")
      (node (ref "C41") (pin "1") (pinfunction "1_1") (pintype "passive"))
      (node (ref "R34") (pin "1") (pinfunction "1_1") (pintype "passive"))
      (node (ref "U16") (pin "3") (pinfunction "+IN_3") (pintype "passive"))
    )
    (net (code "63") (name "Net-(U16--IN)") (class "Default")
      (node (ref "R11") (pin "2") (pinfunction "2_2") (pintype "passive"))
      (node (ref "R12") (pin "1") (pinfunction "1_1") (pintype "passive"))
      (node (ref "U16") (pin "4") (pinfunction "-IN_4") (pintype "passive"))
    )
    (net (code "64") (name "Net-(U17-ADJ)") (class "Default")
      (node (ref "R26") (pin "1") (pinfunction "1_1") (pintype "passive"))
      (node (ref "R28") (pin "2") (pinfunction "2_2") (pintype "passive"))
      (node (ref "U17") (pin "2") (pinfunction "ADJ_2") (pintype "passive"))
    )
    (net (code "65") (name "Net-(U18-ADJ)") (class "Default")
      (node (ref "R27") (pin "1") (pinfunction "1_1") (pintype "passive"))
      (node (ref "R29") (pin "2") (pinfunction "2_2") (pintype "passive"))
      (node (ref "U18") (pin "2") (pinfunction "ADJ_2") (pintype "passive"))
    )
    (net (code "66") (name "unconnected-(U1-C-Pad5)") (class "Default")
      (node (ref "U1") (pin "5") (pinfunction "C_5") (pintype "passive"))
    )
    (net (code "67") (name "unconnected-(U1-D-Pad6)") (class "Default")
      (node (ref "U1") (pin "6") (pinfunction "D_6") (pintype "passive"))
    )
    (net (code "68") (name "unconnected-(U1-G-Pad12)") (class "Default")
      (node (ref "U1") (pin "12") (pinfunction "G_12") (pintype "passive"))
    )
    (net (code "69") (name "unconnected-(U1-H-Pad13)") (class "Default")
      (node (ref "U1") (pin "13") (pinfunction "H_13") (pintype "passive"))
    )
    (net (code "70") (name "unconnected-(U1-J-Pad3)") (class "Default")
      (node (ref "U1") (pin "3") (pinfunction "J_3") (pintype "passive"))
    )
    (net (code "71") (name "unconnected-(U1-L-Pad10)") (class "Default")
      (node (ref "U1") (pin "10") (pinfunction "L_10") (pintype "passive"))
    )
    (net (code "72") (name "unconnected-(U12-C-Pad5)") (class "Default")
      (node (ref "U12") (pin "5") (pinfunction "C_5") (pintype "passive"))
    )
    (net (code "73") (name "unconnected-(U12-D-Pad6)") (class "Default")
      (node (ref "U12") (pin "6") (pinfunction "D_6") (pintype "passive"))
    )
    (net (code "74") (name "unconnected-(U12-E-Pad8)") (class "Default")
      (node (ref "U12") (pin "8") (pinfunction "E_8") (pintype "passive"))
    )
    (net (code "75") (name "unconnected-(U12-F-Pad9)") (class "Default")
      (node (ref "U12") (pin "9") (pinfunction "F_9") (pintype "passive"))
    )
    (net (code "76") (name "unconnected-(U12-K-Pad4)") (class "Default")
      (node (ref "U12") (pin "4") (pinfunction "K_4") (pintype "passive"))
    )
    (net (code "77") (name "unconnected-(U12-L-Pad10)") (class "Default")
      (node (ref "U12") (pin "10") (pinfunction "L_10") (pintype "passive"))
    )
  )
)
